# Power_Supply.net
KiCad netlist of a schematic drawn in Altium Designer
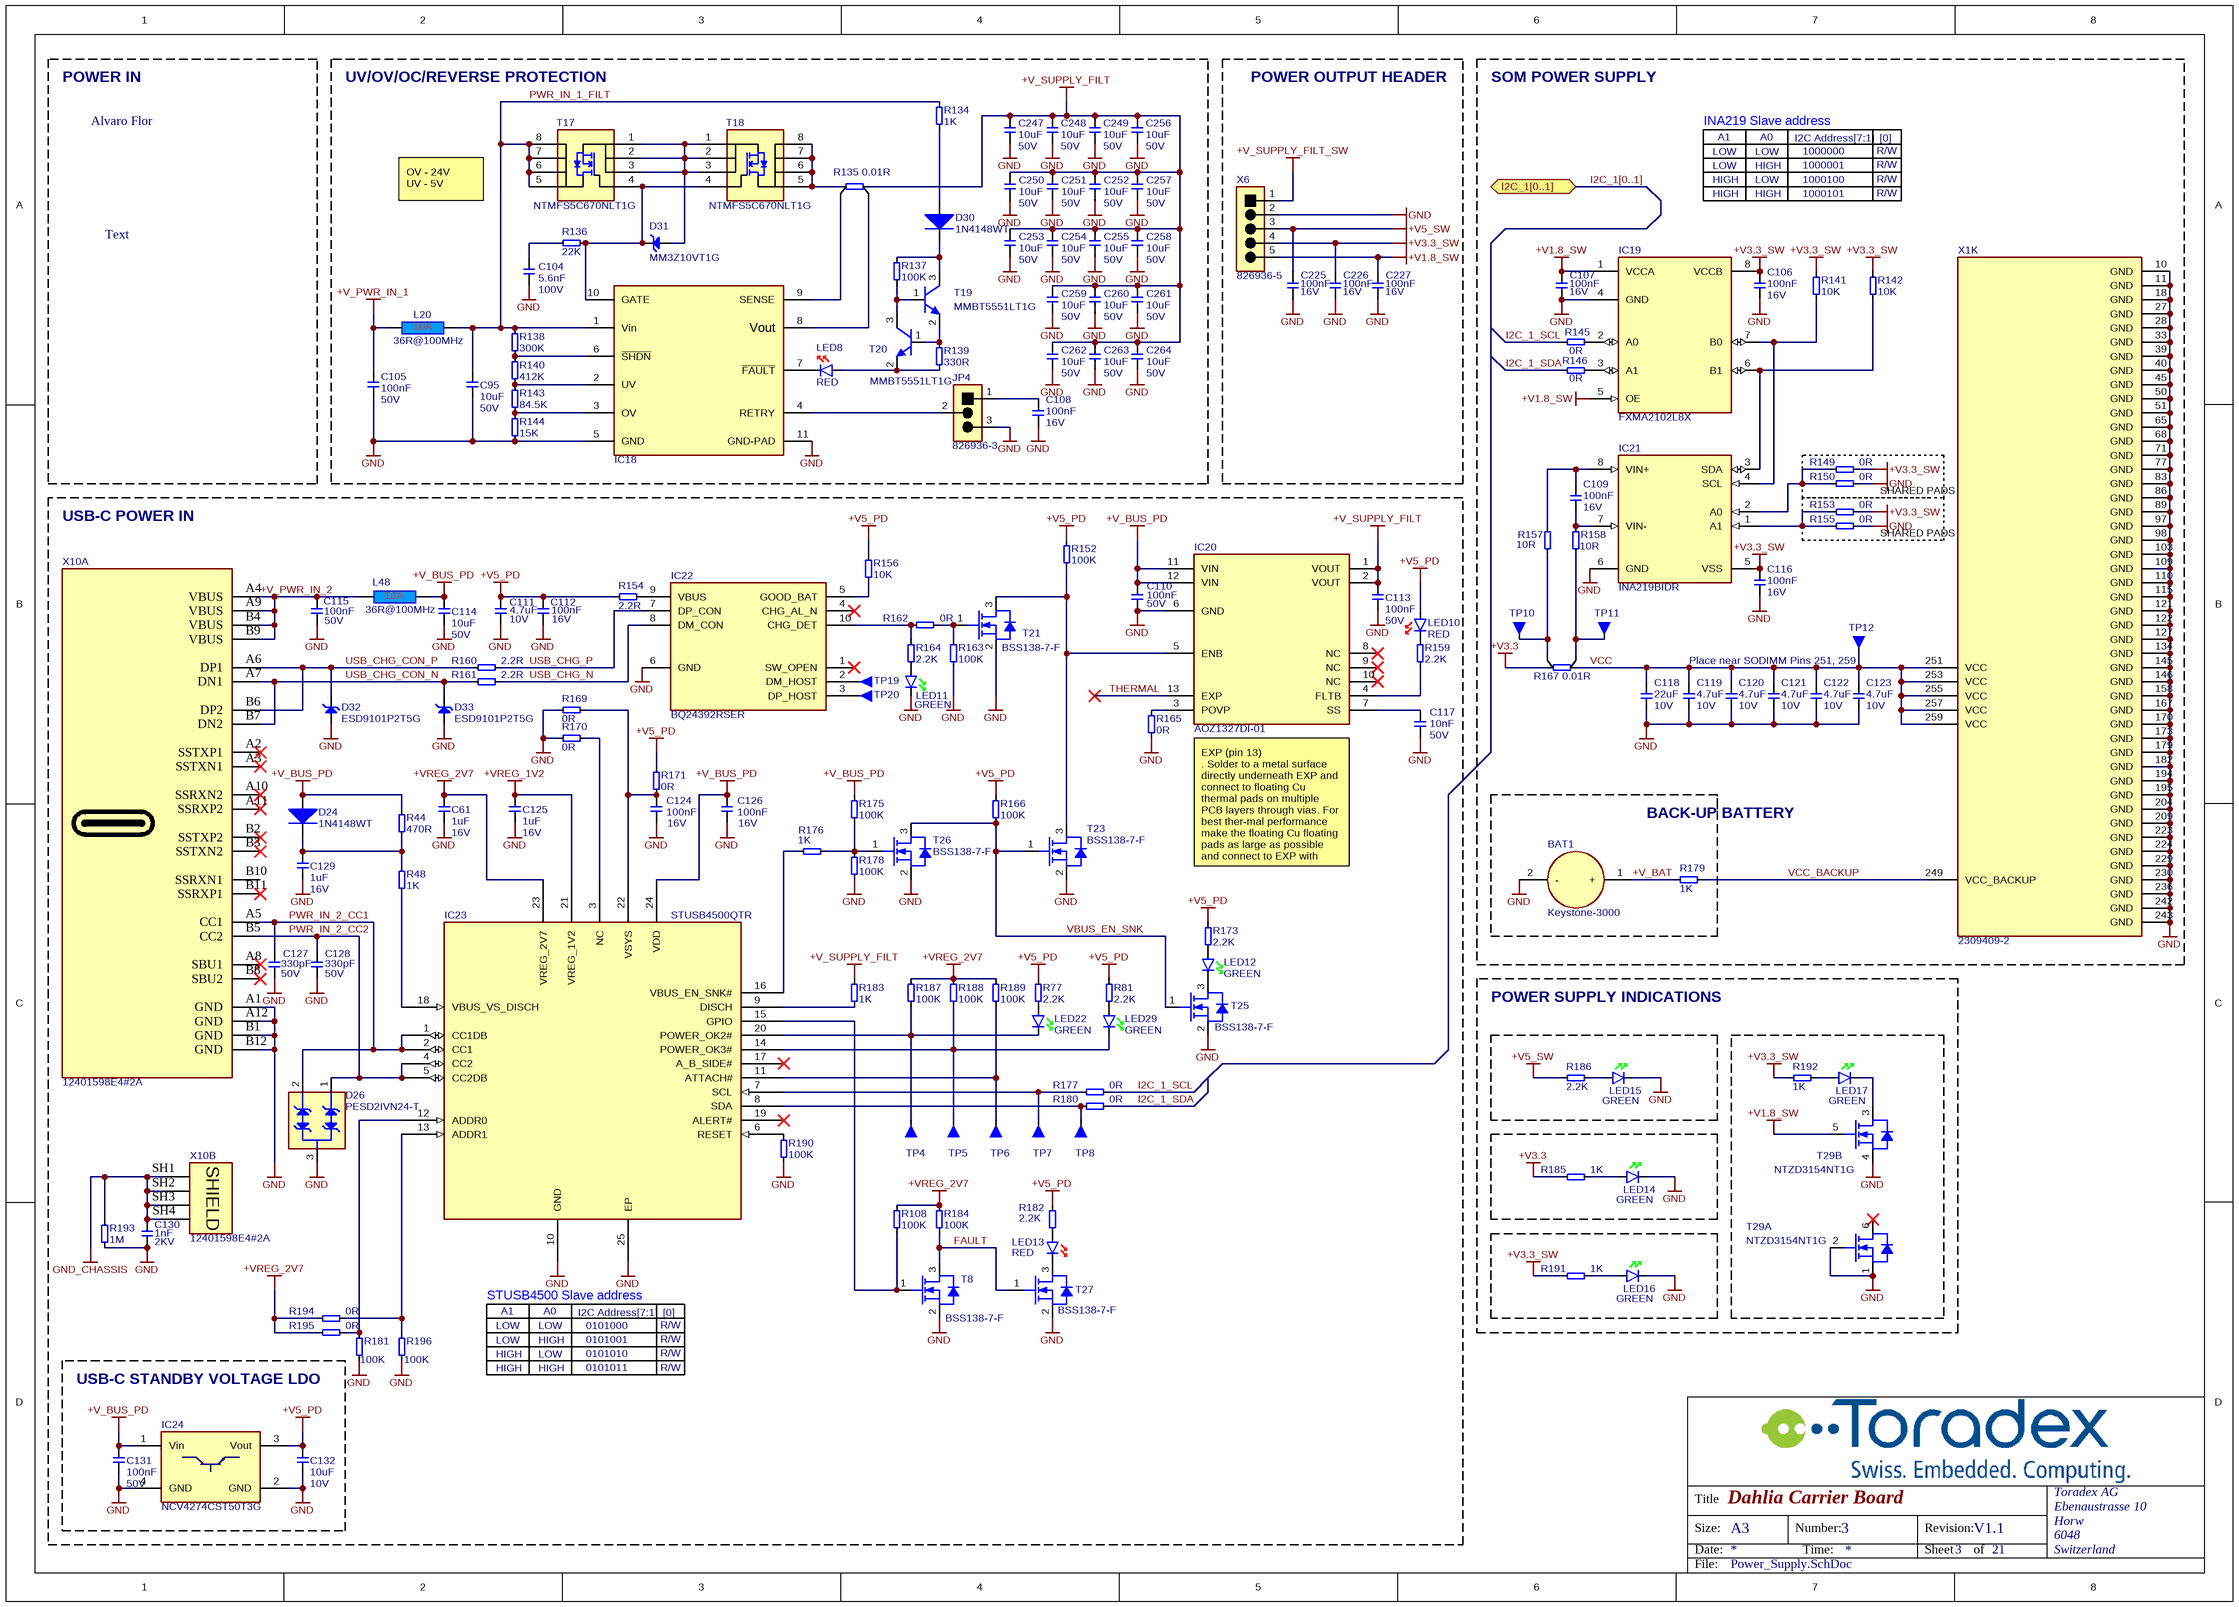
[diagram p0: Power_Supply.SchDoc]

(export (version "E")
  (design (tool "Eeschema 10.0.6"))
  (components
    (comp (ref "BAT1")
      (value "Keystone-3000")
      (footprint "T_Keystone_3000")
      (description "Battery Holder")
      (fields (field (name "MANUFACTURER PART NO.") "3000"))
      (libsource (lib "Dahlia Carrier Board") (part "BAT-Keystone-3000"))
    )
    (comp (ref "C61")
      (value "1uF")
      (footprint "CAPC1005X60N")
      (description "Capacitor Ceramic X5R 1uF 16V 20% 0402")
      (fields (field (name "TOLERANCE") "20%") (field (name "RATING") "16V"))
      (libsource (lib "Dahlia Carrier Board") (part "C-X5R-1uF-16V-20%-0402"))
    )
    (comp (ref "C95")
      (value "10uF")
      (footprint "T_CAPC1206X60N")
      (description "Capacitor Ceramic X5R 10uF 50V 20% 1206")
      (fields (field (name "TOLERANCE") "20%") (field (name "RATING") "50V"))
      (libsource (lib "Dahlia Carrier Board") (part "C-X5R-10uF-50V-20%-1206"))
    )
    (comp (ref "C104")
      (value "5.6nF")
      (footprint "T_CAPC1206X180N")
      (description "Capacitor Ceramic X7R 5.6nF 100V 10% 1206")
      (fields (field (name "TOLERANCE") "10%") (field (name "RATING") "100V"))
      (libsource (lib "Dahlia Carrier Board") (part "C-X7R-5.6n-100V-10%-1206"))
    )
    (comp (ref "C105")
      (value "100nF")
      (footprint "CAPC1005X60N")
      (description "Capacitor Ceramic X7R 100nF 50V 10% 0402")
      (fields (field (name "TOLERANCE") "10%") (field (name "RATING") "50V"))
      (libsource (lib "Dahlia Carrier Board") (part "C-X7R-100nF-50V-10%-0402"))
    )
    (comp (ref "C106")
      (value "100nF")
      (footprint "CAPC1005X60N")
      (description "Capacitor Ceramic X7R 100nF 16V 10% 0402")
      (fields (field (name "TOLERANCE") "10%") (field (name "RATING") "16V"))
      (libsource (lib "Dahlia Carrier Board") (part "C-X7R-100nF-16V-10%-0402"))
    )
    (comp (ref "C107")
      (value "100nF")
      (footprint "CAPC1005X60N")
      (description "Capacitor Ceramic X7R 100nF 16V 10% 0402")
      (fields (field (name "TOLERANCE") "10%") (field (name "RATING") "16V"))
      (libsource (lib "Dahlia Carrier Board") (part "C-X7R-100nF-16V-10%-0402"))
    )
    (comp (ref "C108")
      (value "100nF")
      (footprint "CAPC1005X60N")
      (description "Capacitor Ceramic X7R 100nF 16V 10% 0402")
      (fields (field (name "TOLERANCE") "10%") (field (name "RATING") "16V"))
      (libsource (lib "Dahlia Carrier Board") (part "C-X7R-100nF-16V-10%-0402"))
    )
    (comp (ref "C109")
      (value "100nF")
      (footprint "CAPC1005X60N")
      (description "Capacitor Ceramic X7R 100nF 16V 10% 0402")
      (fields (field (name "TOLERANCE") "10%") (field (name "RATING") "16V"))
      (libsource (lib "Dahlia Carrier Board") (part "C-X7R-100nF-16V-10%-0402"))
    )
    (comp (ref "C110")
      (value "100nF")
      (footprint "CAPC1005X60N")
      (description "Capacitor Ceramic X7R 100nF 50V 10% 0402")
      (fields (field (name "TOLERANCE") "10%") (field (name "RATING") "50V"))
      (libsource (lib "Dahlia Carrier Board") (part "C-X7R-100nF-50V-10%-0402"))
    )
    (comp (ref "C111")
      (value "4.7uF")
      (footprint "T_CAPC0603X33N")
      (description "Capacitor Ceramic X5R 4.7uF 10V 10% 0603")
      (fields (field (name "TOLERANCE") "10%") (field (name "RATING") "10V"))
      (libsource (lib "Dahlia Carrier Board") (part "C-X5R-4.7uF-10V-10%-0603"))
    )
    (comp (ref "C112")
      (value "100nF")
      (footprint "CAPC1005X60N")
      (description "Capacitor Ceramic X7R 100nF 16V 10% 0402")
      (fields (field (name "TOLERANCE") "10%") (field (name "RATING") "16V"))
      (libsource (lib "Dahlia Carrier Board") (part "C-X7R-100nF-16V-10%-0402"))
    )
    (comp (ref "C113")
      (value "100nF")
      (footprint "CAPC1005X60N")
      (description "Capacitor Ceramic X7R 100nF 50V 10% 0402")
      (fields (field (name "TOLERANCE") "10%") (field (name "RATING") "50V"))
      (libsource (lib "Dahlia Carrier Board") (part "C-X7R-100nF-50V-10%-0402"))
    )
    (comp (ref "C114")
      (value "10uF")
      (footprint "T_CAPC1206X60N")
      (description "Capacitor Ceramic X5R 10uF 50V 20% 1206")
      (fields (field (name "TOLERANCE") "20%") (field (name "RATING") "50V"))
      (libsource (lib "Dahlia Carrier Board") (part "C-X5R-10uF-50V-20%-1206"))
    )
    (comp (ref "C115")
      (value "100nF")
      (footprint "CAPC1005X60N")
      (description "Capacitor Ceramic X7R 100nF 50V 10% 0402")
      (fields (field (name "TOLERANCE") "10%") (field (name "RATING") "50V"))
      (libsource (lib "Dahlia Carrier Board") (part "C-X7R-100nF-50V-10%-0402"))
    )
    (comp (ref "C116")
      (value "100nF")
      (footprint "CAPC1005X60N")
      (description "Capacitor Ceramic X7R 100nF 16V 10% 0402")
      (fields (field (name "TOLERANCE") "10%") (field (name "RATING") "16V"))
      (libsource (lib "Dahlia Carrier Board") (part "C-X7R-100nF-16V-10%-0402"))
    )
    (comp (ref "C117")
      (value "10nF")
      (footprint "CAPC1005X60N")
      (description "Capacitor Ceramic X7R 10nF 50V 10% 0402")
      (fields (field (name "TOLERANCE") "10%") (field (name "RATING") "50V"))
      (libsource (lib "Dahlia Carrier Board") (part "C-X7R-10nF-50V-10%-0402"))
    )
    (comp (ref "C118")
      (value "22uF")
      (footprint "T_CAPC0805X125N")
      (description "Capacitor Ceramic X5R 22uF 10V 20% 0805")
      (fields (field (name "TOLERANCE") "20%") (field (name "RATING") "10V"))
      (libsource (lib "Dahlia Carrier Board") (part "C-X5R-22uF-10V-20%-0805"))
    )
    (comp (ref "C119")
      (value "4.7uF")
      (footprint "T_CAPC0603X33N")
      (description "Capacitor Ceramic X5R 4.7uF 10V 10% 0603")
      (fields (field (name "TOLERANCE") "10%") (field (name "RATING") "10V"))
      (libsource (lib "Dahlia Carrier Board") (part "C-X5R-4.7uF-10V-10%-0603"))
    )
    (comp (ref "C120")
      (value "4.7uF")
      (footprint "T_CAPC0603X33N")
      (description "Capacitor Ceramic X5R 4.7uF 10V 10% 0603")
      (fields (field (name "TOLERANCE") "10%") (field (name "RATING") "10V"))
      (libsource (lib "Dahlia Carrier Board") (part "C-X5R-4.7uF-10V-10%-0603"))
    )
    (comp (ref "C121")
      (value "4.7uF")
      (footprint "T_CAPC0603X33N")
      (description "Capacitor Ceramic X5R 4.7uF 10V 10% 0603")
      (fields (field (name "TOLERANCE") "10%") (field (name "RATING") "10V"))
      (libsource (lib "Dahlia Carrier Board") (part "C-X5R-4.7uF-10V-10%-0603"))
    )
    (comp (ref "C122")
      (value "4.7uF")
      (footprint "T_CAPC0603X33N")
      (description "Capacitor Ceramic X5R 4.7uF 10V 10% 0603")
      (fields (field (name "TOLERANCE") "10%") (field (name "RATING") "10V"))
      (libsource (lib "Dahlia Carrier Board") (part "C-X5R-4.7uF-10V-10%-0603"))
    )
    (comp (ref "C123")
      (value "4.7uF")
      (footprint "T_CAPC0603X33N")
      (description "Capacitor Ceramic X5R 4.7uF 10V 10% 0603")
      (fields (field (name "TOLERANCE") "10%") (field (name "RATING") "10V"))
      (libsource (lib "Dahlia Carrier Board") (part "C-X5R-4.7uF-10V-10%-0603"))
    )
    (comp (ref "C124")
      (value "100nF")
      (footprint "CAPC1005X60N")
      (description "Capacitor Ceramic X7R 100nF 16V 10% 0402")
      (fields (field (name "TOLERANCE") "10%") (field (name "RATING") "16V"))
      (libsource (lib "Dahlia Carrier Board") (part "C-X7R-100nF-16V-10%-0402"))
    )
    (comp (ref "C125")
      (value "1uF")
      (footprint "CAPC1005X60N")
      (description "Capacitor Ceramic X5R 1uF 16V 20% 0402")
      (fields (field (name "TOLERANCE") "20%") (field (name "RATING") "16V"))
      (libsource (lib "Dahlia Carrier Board") (part "C-X5R-1uF-16V-20%-0402"))
    )
    (comp (ref "C126")
      (value "100nF")
      (footprint "CAPC1005X60N")
      (description "Capacitor Ceramic X7R 100nF 16V 10% 0402")
      (fields (field (name "TOLERANCE") "10%") (field (name "RATING") "16V"))
      (libsource (lib "Dahlia Carrier Board") (part "C-X7R-100nF-16V-10%-0402"))
    )
    (comp (ref "C127")
      (value "330pF")
      (footprint "CAPC1005X60N")
      (description "Capacitor Ceramic X7R 330pF 50V 10% 0402")
      (fields (field (name "TOLERANCE") "10%") (field (name "RATING") "50V"))
      (libsource (lib "Dahlia Carrier Board") (part "C-X7R-330pF-50V-10%-0402"))
    )
    (comp (ref "C128")
      (value "330pF")
      (footprint "CAPC1005X60N")
      (description "Capacitor Ceramic X7R 330pF 50V 10% 0402")
      (fields (field (name "TOLERANCE") "10%") (field (name "RATING") "50V"))
      (libsource (lib "Dahlia Carrier Board") (part "C-X7R-330pF-50V-10%-0402"))
    )
    (comp (ref "C129")
      (value "1uF")
      (footprint "CAPC1005X60N")
      (description "Capacitor Ceramic X5R 1uF 16V 20% 0402")
      (fields (field (name "TOLERANCE") "20%") (field (name "RATING") "16V"))
      (libsource (lib "Dahlia Carrier Board") (part "C-X5R-1uF-16V-20%-0402"))
    )
    (comp (ref "C130")
      (value "1nF")
      (footprint "T_CAPC1206X180N")
      (description "Capacitor Ceramic X7R 1nF 2KV 10% 1206")
      (fields (field (name "TOLERANCE") "10%") (field (name "RATING") "2KV"))
      (libsource (lib "Dahlia Carrier Board") (part "C-X7R-1nF-2KV-10%-1206"))
    )
    (comp (ref "C131")
      (value "100nF")
      (footprint "CAPC1005X60N")
      (description "Capacitor Ceramic X7R 100nF 50V 10% 0402")
      (fields (field (name "TOLERANCE") "10%") (field (name "RATING") "50V"))
      (libsource (lib "Dahlia Carrier Board") (part "C-X7R-100nF-50V-10%-0402"))
    )
    (comp (ref "C132")
      (value "10uF")
      (footprint "T_CAPC0603X33N")
      (description "Capacitor Ceramic X5R 10uF 10V 20% 0603")
      (fields (field (name "TOLERANCE") "20%") (field (name "RATING") "10V"))
      (libsource (lib "Dahlia Carrier Board") (part "C-X5R-10uF-10V-20%-0603"))
    )
    (comp (ref "C225")
      (value "100nF")
      (footprint "CAPC1005X60N")
      (description "Capacitor Ceramic X7R 100nF 16V 10% 0402")
      (fields (field (name "TOLERANCE") "10%") (field (name "RATING") "16V"))
      (libsource (lib "Dahlia Carrier Board") (part "C-X7R-100nF-16V-10%-0402"))
    )
    (comp (ref "C226")
      (value "100nF")
      (footprint "CAPC1005X60N")
      (description "Capacitor Ceramic X7R 100nF 16V 10% 0402")
      (fields (field (name "TOLERANCE") "10%") (field (name "RATING") "16V"))
      (libsource (lib "Dahlia Carrier Board") (part "C-X7R-100nF-16V-10%-0402"))
    )
    (comp (ref "C227")
      (value "100nF")
      (footprint "CAPC1005X60N")
      (description "Capacitor Ceramic X7R 100nF 16V 10% 0402")
      (fields (field (name "TOLERANCE") "10%") (field (name "RATING") "16V"))
      (libsource (lib "Dahlia Carrier Board") (part "C-X7R-100nF-16V-10%-0402"))
    )
    (comp (ref "C247")
      (value "10uF")
      (footprint "T_CAPC1206X60N")
      (description "Capacitor Ceramic X5R 10uF 50V 20% 1206")
      (fields (field (name "TOLERANCE") "20%") (field (name "RATING") "50V"))
      (libsource (lib "Dahlia Carrier Board") (part "C-X5R-10uF-50V-20%-1206"))
    )
    (comp (ref "C248")
      (value "10uF")
      (footprint "T_CAPC1206X60N")
      (description "Capacitor Ceramic X5R 10uF 50V 20% 1206")
      (fields (field (name "TOLERANCE") "20%") (field (name "RATING") "50V"))
      (libsource (lib "Dahlia Carrier Board") (part "C-X5R-10uF-50V-20%-1206"))
    )
    (comp (ref "C249")
      (value "10uF")
      (footprint "T_CAPC1206X60N")
      (description "Capacitor Ceramic X5R 10uF 50V 20% 1206")
      (fields (field (name "TOLERANCE") "20%") (field (name "RATING") "50V"))
      (libsource (lib "Dahlia Carrier Board") (part "C-X5R-10uF-50V-20%-1206"))
    )
    (comp (ref "C250")
      (value "10uF")
      (footprint "T_CAPC1206X60N")
      (description "Capacitor Ceramic X5R 10uF 50V 20% 1206")
      (fields (field (name "TOLERANCE") "20%") (field (name "RATING") "50V"))
      (libsource (lib "Dahlia Carrier Board") (part "C-X5R-10uF-50V-20%-1206"))
    )
    (comp (ref "C251")
      (value "10uF")
      (footprint "T_CAPC1206X60N")
      (description "Capacitor Ceramic X5R 10uF 50V 20% 1206")
      (fields (field (name "TOLERANCE") "20%") (field (name "RATING") "50V"))
      (libsource (lib "Dahlia Carrier Board") (part "C-X5R-10uF-50V-20%-1206"))
    )
    (comp (ref "C252")
      (value "10uF")
      (footprint "T_CAPC1206X60N")
      (description "Capacitor Ceramic X5R 10uF 50V 20% 1206")
      (fields (field (name "TOLERANCE") "20%") (field (name "RATING") "50V"))
      (libsource (lib "Dahlia Carrier Board") (part "C-X5R-10uF-50V-20%-1206"))
    )
    (comp (ref "C253")
      (value "10uF")
      (footprint "T_CAPC1206X60N")
      (description "Capacitor Ceramic X5R 10uF 50V 20% 1206")
      (fields (field (name "TOLERANCE") "20%") (field (name "RATING") "50V"))
      (libsource (lib "Dahlia Carrier Board") (part "C-X5R-10uF-50V-20%-1206"))
    )
    (comp (ref "C254")
      (value "10uF")
      (footprint "T_CAPC1206X60N")
      (description "Capacitor Ceramic X5R 10uF 50V 20% 1206")
      (fields (field (name "TOLERANCE") "20%") (field (name "RATING") "50V"))
      (libsource (lib "Dahlia Carrier Board") (part "C-X5R-10uF-50V-20%-1206"))
    )
    (comp (ref "C255")
      (value "10uF")
      (footprint "T_CAPC1206X60N")
      (description "Capacitor Ceramic X5R 10uF 50V 20% 1206")
      (fields (field (name "TOLERANCE") "20%") (field (name "RATING") "50V"))
      (libsource (lib "Dahlia Carrier Board") (part "C-X5R-10uF-50V-20%-1206"))
    )
    (comp (ref "C256")
      (value "10uF")
      (footprint "T_CAPC1206X60N")
      (description "Capacitor Ceramic X5R 10uF 50V 20% 1206")
      (fields (field (name "TOLERANCE") "20%") (field (name "RATING") "50V"))
      (libsource (lib "Dahlia Carrier Board") (part "C-X5R-10uF-50V-20%-1206"))
    )
    (comp (ref "C257")
      (value "10uF")
      (footprint "T_CAPC1206X60N")
      (description "Capacitor Ceramic X5R 10uF 50V 20% 1206")
      (fields (field (name "TOLERANCE") "20%") (field (name "RATING") "50V"))
      (libsource (lib "Dahlia Carrier Board") (part "C-X5R-10uF-50V-20%-1206"))
    )
    (comp (ref "C258")
      (value "10uF")
      (footprint "T_CAPC1206X60N")
      (description "Capacitor Ceramic X5R 10uF 50V 20% 1206")
      (fields (field (name "TOLERANCE") "20%") (field (name "RATING") "50V"))
      (libsource (lib "Dahlia Carrier Board") (part "C-X5R-10uF-50V-20%-1206"))
    )
    (comp (ref "C259")
      (value "10uF")
      (footprint "T_CAPC1206X60N")
      (description "Capacitor Ceramic X5R 10uF 50V 20% 1206")
      (fields (field (name "TOLERANCE") "20%") (field (name "RATING") "50V"))
      (libsource (lib "Dahlia Carrier Board") (part "C-X5R-10uF-50V-20%-1206"))
    )
    (comp (ref "C260")
      (value "10uF")
      (footprint "T_CAPC1206X60N")
      (description "Capacitor Ceramic X5R 10uF 50V 20% 1206")
      (fields (field (name "TOLERANCE") "20%") (field (name "RATING") "50V"))
      (libsource (lib "Dahlia Carrier Board") (part "C-X5R-10uF-50V-20%-1206"))
    )
    (comp (ref "C261")
      (value "10uF")
      (footprint "T_CAPC1206X60N")
      (description "Capacitor Ceramic X5R 10uF 50V 20% 1206")
      (fields (field (name "TOLERANCE") "20%") (field (name "RATING") "50V"))
      (libsource (lib "Dahlia Carrier Board") (part "C-X5R-10uF-50V-20%-1206"))
    )
    (comp (ref "C262")
      (value "10uF")
      (footprint "T_CAPC1206X60N")
      (description "Capacitor Ceramic X5R 10uF 50V 20% 1206")
      (fields (field (name "TOLERANCE") "20%") (field (name "RATING") "50V"))
      (libsource (lib "Dahlia Carrier Board") (part "C-X5R-10uF-50V-20%-1206"))
    )
    (comp (ref "C263")
      (value "10uF")
      (footprint "T_CAPC1206X60N")
      (description "Capacitor Ceramic X5R 10uF 50V 20% 1206")
      (fields (field (name "TOLERANCE") "20%") (field (name "RATING") "50V"))
      (libsource (lib "Dahlia Carrier Board") (part "C-X5R-10uF-50V-20%-1206"))
    )
    (comp (ref "C264")
      (value "10uF")
      (footprint "T_CAPC1206X60N")
      (description "Capacitor Ceramic X5R 10uF 50V 20% 1206")
      (fields (field (name "TOLERANCE") "20%") (field (name "RATING") "50V"))
      (libsource (lib "Dahlia Carrier Board") (part "C-X5R-10uF-50V-20%-1206"))
    )
    (comp (ref "D24")
      (value "1N4148WT")
      (footprint "SOD-523F")
      (description "Diode Standard 75V 200mA Surface Mount SOD-523F")
      (fields (field (name "MANUFACTURER PART NO.") "1N4148WT"))
      (libsource (lib "Dahlia Carrier Board") (part "D-OnSemi-1N4148WT"))
    )
    (comp (ref "D26")
      (value "PESD2IVN24-T")
      (footprint "SOT95P230X110-3N")
      (description "TVS Array low cap")
      (fields (field (name "MANUFACTURER PART NO.") "PESD2IVN24-T"))
      (libsource (lib "Dahlia Carrier Board") (part "D-Nexperia-PESD2IVN24-T"))
    )
    (comp (ref "D30")
      (value "1N4148WT")
      (footprint "SOD-523F")
      (description "Diode Standard 75V 200mA Surface Mount SOD-523F")
      (fields (field (name "MANUFACTURER PART NO.") "1N4148WT"))
      (libsource (lib "Dahlia Carrier Board") (part "D-OnSemi-1N4148WT"))
    )
    (comp (ref "D31")
      (value "MM3Z10VT1G")
      (footprint "T_SOD-323")
      (description "DIODE ZENER 10V 300MW SOD323")
      (fields (field (name "MANUFACTURER PART NO.") "MM3Z10VT1G"))
      (libsource (lib "Dahlia Carrier Board") (part "D-OnSemi-MM3Z10VT1G"))
    )
    (comp (ref "D32")
      (value "ESD9101P2T5G")
      (footprint "SOD-923")
      (description "ESD Protection Diode")
      (fields (field (name "MANUFACTURER PART NO.") "ESD9101P2T5G"))
      (libsource (lib "Dahlia Carrier Board") (part "D-OnSemi-ESD9101P2T5G"))
    )
    (comp (ref "D33")
      (value "ESD9101P2T5G")
      (footprint "SOD-923")
      (description "ESD Protection Diode")
      (fields (field (name "MANUFACTURER PART NO.") "ESD9101P2T5G"))
      (libsource (lib "Dahlia Carrier Board") (part "D-OnSemi-ESD9101P2T5G"))
    )
    (comp (ref "IC18")
      (value "LTC4368IDD-2#PBF")
      (footprint "IC-DFN50P300X300X75-10N")
      (description "Reverse Protection Controller with Bidirectional Circuit Breaker")
      (libsource (lib "Dahlia Carrier Board") (part "IC-LIN-LTC4368IDD-2#PBF"))
    )
    (comp (ref "IC19")
      (value "FXMA2102L8X")
      (footprint "IC-MicroPak50P160X2160X55-8N")
      (description "Voltage Level Translator for I2C Applications")
      (fields (field (name "MANUFACTURER PART NO.") "FXMA2102L8X"))
      (libsource (lib "Dahlia Carrier Board") (part "IC-ONsemi-FXMA2102L8X"))
    )
    (comp (ref "IC20")
      (value "AOZ1327DI-01")
      (footprint "IC-A&O-AOZ1327DI-01")
      (description "20V Protection Switch with True Reverse Current Blocking")
      (fields (field (name "MANUFACTURER PART NO.") "AOZ1327DI-01"))
      (libsource (lib "Dahlia Carrier Board") (part "IC-A&O-AOZ1327DI-01"))
    )
    (comp (ref "IC21")
      (value "INA219")
      (footprint "SOIC127P600X173-8N")
      (description "CURRENT/POWER MONITOR with I2C Interface")
      (fields (field (name "MANUFACTURER PART NO.") "INA219BIDR"))
      (libsource (lib "Dahlia Carrier Board") (part "IC-TI-INA219BIDR"))
    )
    (comp (ref "IC22")
      (value "BQ24392RSER")
      (footprint "IC-TI-BQ24392RSER")
      (description "USB Charger Detection")
      (fields (field (name "MANUFACTURER PART NO.") "BQ24392RSER"))
      (libsource (lib "Dahlia Carrier Board") (part "IC-TI-BQ24392RSER"))
    )
    (comp (ref "IC23")
      (value "STUSB4500QTR")
      (footprint "T_STUSB4500QTR")
      (description "Standalone USB PD sink controller with short-to-VBUS protections")
      (libsource (lib "Dahlia Carrier Board") (part "IC-ST-STUSB4500QTR"))
    )
    (comp (ref "IC24")
      (value "NCV4274CST50T3G")
      (footprint "T_ON_NCV4264-2ST50T3G")
      (description "LDO regulator, Vout = 5V, Iout(max) = 0.4A, Vin = 5.5V to 40V, SOT-223")
      (fields (field (name "MANUFACTURER PART NO.") "NCV4274CST50T3G"))
      (libsource (lib "Dahlia Carrier Board") (part "IC-ON-NCV4274CST50T3G"))
    )
    (comp (ref "JP4")
      (value "826936-3")
      (footprint "T_TYCO_826936-3")
      (description "Jumper, 3-Pin")
      (fields (field (name "MANUFACTURER PART NO.") "826936-3"))
      (libsource (lib "Dahlia Carrier Board") (part "CON-Tyco-826936-3-1X3-2.54mm-JP_1"))
    )
    (comp (ref "L20")
      (value "36R@100MHz")
      (footprint "T_Laird_35F0121-0SR-10")
      (description "Power Supply FB 10A")
      (fields (field (name "TOLERANCE") "25%"))
      (libsource (lib "Dahlia Carrier Board") (part "L-Laird-35F0121-0SR-10-10A-25%"))
    )
    (comp (ref "L48")
      (value "36R@100MHz")
      (footprint "T_Laird_35F0121-0SR-10")
      (description "Power Supply FB 10A")
      (fields (field (name "TOLERANCE") "25%"))
      (libsource (lib "Dahlia Carrier Board") (part "L-Laird-35F0121-0SR-10-10A-25%"))
    )
    (comp (ref "LED8")
      (value "LTST-C190KRKT")
      (footprint "T_Liteon_LTST-C190KRKT")
      (description "LED red, Lite-On LTST-C190KRKT")
      (fields (field (name "COLOR") "RED"))
      (libsource (lib "Dahlia Carrier Board") (part "LED-LiteOn-LTST-C190KRKT"))
    )
    (comp (ref "LED10")
      (value "LTST-C190KRKT")
      (footprint "T_Liteon_LTST-C190KRKT")
      (description "LED red, Lite-On LTST-C190KRKT")
      (fields (field (name "COLOR") "RED"))
      (libsource (lib "Dahlia Carrier Board") (part "LED-LiteOn-LTST-C190KRKT"))
    )
    (comp (ref "LED11")
      (value "LTST-C190GKT")
      (footprint "T_Liteon_LTST-C190GKT")
      (description "LED green Lite-ON LTST-C190GKT")
      (fields (field (name "COLOR") "GREEN"))
      (libsource (lib "Dahlia Carrier Board") (part "LED-LiteOn-LTST-C190GKT"))
    )
    (comp (ref "LED12")
      (value "LTST-C190GKT")
      (footprint "T_Liteon_LTST-C190GKT")
      (description "LED green Lite-ON LTST-C190GKT")
      (fields (field (name "COLOR") "GREEN"))
      (libsource (lib "Dahlia Carrier Board") (part "LED-LiteOn-LTST-C190GKT"))
    )
    (comp (ref "LED13")
      (value "LTST-C190KRKT")
      (footprint "T_Liteon_LTST-C190KRKT")
      (description "LED red, Lite-On LTST-C190KRKT")
      (fields (field (name "COLOR") "RED"))
      (libsource (lib "Dahlia Carrier Board") (part "LED-LiteOn-LTST-C190KRKT"))
    )
    (comp (ref "LED14")
      (value "LTST-C190GKT")
      (footprint "T_Liteon_LTST-C190GKT")
      (description "LED green Lite-ON LTST-C190GKT")
      (fields (field (name "COLOR") "GREEN"))
      (libsource (lib "Dahlia Carrier Board") (part "LED-LiteOn-LTST-C190GKT"))
    )
    (comp (ref "LED15")
      (value "LTST-C190GKT")
      (footprint "T_Liteon_LTST-C190GKT")
      (description "LED green Lite-ON LTST-C190GKT")
      (fields (field (name "COLOR") "GREEN"))
      (libsource (lib "Dahlia Carrier Board") (part "LED-LiteOn-LTST-C190GKT"))
    )
    (comp (ref "LED16")
      (value "LTST-C190GKT")
      (footprint "T_Liteon_LTST-C190GKT")
      (description "LED green Lite-ON LTST-C190GKT")
      (fields (field (name "COLOR") "GREEN"))
      (libsource (lib "Dahlia Carrier Board") (part "LED-LiteOn-LTST-C190GKT"))
    )
    (comp (ref "LED17")
      (value "LTST-C190GKT")
      (footprint "T_Liteon_LTST-C190GKT")
      (description "LED green Lite-ON LTST-C190GKT")
      (fields (field (name "COLOR") "GREEN"))
      (libsource (lib "Dahlia Carrier Board") (part "LED-LiteOn-LTST-C190GKT"))
    )
    (comp (ref "LED22")
      (value "LTST-C190GKT")
      (footprint "T_Liteon_LTST-C190GKT")
      (description "LED green Lite-ON LTST-C190GKT")
      (fields (field (name "COLOR") "GREEN"))
      (libsource (lib "Dahlia Carrier Board") (part "LED-LiteOn-LTST-C190GKT"))
    )
    (comp (ref "LED29")
      (value "LTST-C190GKT")
      (footprint "T_Liteon_LTST-C190GKT")
      (description "LED green Lite-ON LTST-C190GKT")
      (fields (field (name "COLOR") "GREEN"))
      (libsource (lib "Dahlia Carrier Board") (part "LED-LiteOn-LTST-C190GKT"))
    )
    (comp (ref "R44")
      (value "470R")
      (footprint "T_RESC0603X30N")
      (description "Resistor 470 Ohm 63mW 1% 0603")
      (fields (field (name "TOLERANCE") "1%"))
      (libsource (lib "Dahlia Carrier Board") (part "R-470R-63mW-1%-0603"))
    )
    (comp (ref "R48")
      (value "1K")
      (footprint "T_RESC0603X30N")
      (description "Resistor 1 Kohm 63mW 5% 0603")
      (fields (field (name "TOLERANCE") "5%"))
      (libsource (lib "Dahlia Carrier Board") (part "R-1K-63mW-5%-0603"))
    )
    (comp (ref "R77")
      (value "2.2K")
      (footprint "RESC1005X40N")
      (description "Resistor 2.2 Kohm 63mW 5% 0402")
      (fields (field (name "TOLERANCE") "5%"))
      (libsource (lib "Dahlia Carrier Board") (part "R-2.2K-63mW-5%-0402"))
    )
    (comp (ref "R81")
      (value "2.2K")
      (footprint "RESC1005X40N")
      (description "Resistor 2.2 Kohm 63mW 5% 0402")
      (fields (field (name "TOLERANCE") "5%"))
      (libsource (lib "Dahlia Carrier Board") (part "R-2.2K-63mW-5%-0402"))
    )
    (comp (ref "R108")
      (value "100K")
      (footprint "RESC1005X40N")
      (description "Resistor 100 Kohm 63mW 5% 0402")
      (fields (field (name "TOLERANCE") "5%"))
      (libsource (lib "Dahlia Carrier Board") (part "R-100K-63mW-5%-0402"))
    )
    (comp (ref "R134")
      (value "1K")
      (footprint "RESC1005X40N")
      (description "Resistor 1 Kohm 63mW 5% 0402")
      (fields (field (name "TOLERANCE") "5%"))
      (libsource (lib "Dahlia Carrier Board") (part "R-1K-63mW-5%-0402"))
    )
    (comp (ref "R135")
      (value "0.01R")
      (footprint "RESWSK1206")
      (fields (field (name "TOLERANCE") "1%") (field (name "MANUFACTURER PART NO.") "WSK1206R0100FEA18"))
      (libsource (lib "Dahlia Carrier Board") (part "R-Vishay-WSK1206R0100FEA18"))
    )
    (comp (ref "R136")
      (value "22K")
      (footprint "RESC3216X75N")
      (description "Resistor 22 Kohm 250mW 1% 1206")
      (fields (field (name "TOLERANCE") "1%"))
      (libsource (lib "Dahlia Carrier Board") (part "R-22K-250mW-1%-1206"))
    )
    (comp (ref "R137")
      (value "100K")
      (footprint "RESC1005X40N")
      (description "Resistor 100 Kohm 63mW 5% 0402")
      (fields (field (name "TOLERANCE") "5%"))
      (libsource (lib "Dahlia Carrier Board") (part "R-100K-63mW-5%-0402"))
    )
    (comp (ref "R138")
      (value "300K")
      (footprint "RESC3216X75N")
      (description "Resistor 300 Kohm 250mW 1% 1206")
      (fields (field (name "TOLERANCE") "1%"))
      (libsource (lib "Dahlia Carrier Board") (part "R-300K-250mW-1%-1206"))
    )
    (comp (ref "R139")
      (value "330R")
      (footprint "RESC1005X40N")
      (description "Resistor 330 ohm 63mW 5% 0402")
      (fields (field (name "TOLERANCE") "5%"))
      (libsource (lib "Dahlia Carrier Board") (part "R-330R-63mW-5%-0402"))
    )
    (comp (ref "R140")
      (value "412K")
      (footprint "RESC3216X75N")
      (description "Resistor 412 Kohm 250mW 1% 1206")
      (fields (field (name "TOLERANCE") "1%"))
      (libsource (lib "Dahlia Carrier Board") (part "R-412K-250mW-1%-1206"))
    )
    (comp (ref "R141")
      (value "10K")
      (footprint "RESC1005X40N")
      (description "Resistor 10 Kohm 63mW 5% 0402")
      (fields (field (name "TOLERANCE") "5%"))
      (libsource (lib "Dahlia Carrier Board") (part "R-10K-63mW-5%-0402"))
    )
    (comp (ref "R142")
      (value "10K")
      (footprint "RESC1005X40N")
      (description "Resistor 10 Kohm 63mW 5% 0402")
      (fields (field (name "TOLERANCE") "5%"))
      (libsource (lib "Dahlia Carrier Board") (part "R-10K-63mW-5%-0402"))
    )
    (comp (ref "R143")
      (value "84.5K")
      (footprint "RESC3216X75N")
      (description "Resistor 84.5 Kohm 250mW 1% 1206")
      (fields (field (name "TOLERANCE") "1%"))
      (libsource (lib "Dahlia Carrier Board") (part "R-84.5K-250mW-1%-1206"))
    )
    (comp (ref "R144")
      (value "15K")
      (footprint "RESC3216X75N")
      (description "Resistor 15 Kohm 250mW 1% 1206")
      (fields (field (name "TOLERANCE") "1%"))
      (libsource (lib "Dahlia Carrier Board") (part "R-15K-250mW-1%-1206"))
    )
    (comp (ref "R145")
      (value "0R")
      (footprint "T_RESC0603X30N")
      (description "Resistor 0 ohm 63mW 1% 0603")
      (fields (field (name "TOLERANCE") "1%"))
      (libsource (lib "Dahlia Carrier Board") (part "R-0R-63mW-1%-0603"))
    )
    (comp (ref "R146")
      (value "0R")
      (footprint "T_RESC0603X30N")
      (description "Resistor 0 ohm 63mW 1% 0603")
      (fields (field (name "TOLERANCE") "1%"))
      (libsource (lib "Dahlia Carrier Board") (part "R-0R-63mW-1%-0603"))
    )
    (comp (ref "R149")
      (value "0R")
      (footprint "T_RESC0603X30N")
      (description "Resistor 0 ohm 63mW 1% 0603")
      (fields (field (name "TOLERANCE") "1%"))
      (libsource (lib "Dahlia Carrier Board") (part "R-0R-63mW-1%-0603"))
    )
    (comp (ref "R150")
      (value "0R")
      (footprint "T_RESC0603X30N")
      (description "Resistor 0 ohm 63mW 1% 0603")
      (fields (field (name "TOLERANCE") "1%"))
      (libsource (lib "Dahlia Carrier Board") (part "R-0R-63mW-1%-0603"))
    )
    (comp (ref "R152")
      (value "100K")
      (footprint "RESC1005X40N")
      (description "Resistor 100 Kohm 63mW 5% 0402")
      (fields (field (name "TOLERANCE") "5%"))
      (libsource (lib "Dahlia Carrier Board") (part "R-100K-63mW-5%-0402"))
    )
    (comp (ref "R153")
      (value "0R")
      (footprint "T_RESC0603X30N")
      (description "Resistor 0 ohm 63mW 1% 0603")
      (fields (field (name "TOLERANCE") "1%"))
      (libsource (lib "Dahlia Carrier Board") (part "R-0R-63mW-1%-0603"))
    )
    (comp (ref "R154")
      (value "2.2R")
      (footprint "T_RESC0603X30N")
      (description "Resistor 2.2 ohm 63mW 5% 0603")
      (fields (field (name "TOLERANCE") "5%"))
      (libsource (lib "Dahlia Carrier Board") (part "R-2.2R-63mW-5%-0603"))
    )
    (comp (ref "R155")
      (value "0R")
      (footprint "T_RESC0603X30N")
      (description "Resistor 0 ohm 63mW 1% 0603")
      (fields (field (name "TOLERANCE") "1%"))
      (libsource (lib "Dahlia Carrier Board") (part "R-0R-63mW-1%-0603"))
    )
    (comp (ref "R156")
      (value "10K")
      (footprint "RESC1005X40N")
      (description "Resistor 10 Kohm 63mW 5% 0402")
      (fields (field (name "TOLERANCE") "5%"))
      (libsource (lib "Dahlia Carrier Board") (part "R-10K-63mW-5%-0402"))
    )
    (comp (ref "R157")
      (value "10R")
      (footprint "RESC1005X40N")
      (description "Resistor 10 ohm 63mW 5% 0402")
      (fields (field (name "TOLERANCE") "5%"))
      (libsource (lib "Dahlia Carrier Board") (part "R-10R-63mW-5%-0402"))
    )
    (comp (ref "R158")
      (value "10R")
      (footprint "RESC1005X40N")
      (description "Resistor 10 ohm 63mW 5% 0402")
      (fields (field (name "TOLERANCE") "5%"))
      (libsource (lib "Dahlia Carrier Board") (part "R-10R-63mW-5%-0402"))
    )
    (comp (ref "R159")
      (value "2.2K")
      (footprint "RESC1005X40N")
      (description "Resistor 2.2 Kohm 63mW 5% 0402")
      (fields (field (name "TOLERANCE") "5%"))
      (libsource (lib "Dahlia Carrier Board") (part "R-2.2K-63mW-5%-0402"))
    )
    (comp (ref "R160")
      (value "2.2R")
      (footprint "T_RESC0603X30N")
      (description "Resistor 2.2 ohm 63mW 5% 0603")
      (fields (field (name "TOLERANCE") "5%"))
      (libsource (lib "Dahlia Carrier Board") (part "R-2.2R-63mW-5%-0603"))
    )
    (comp (ref "R161")
      (value "2.2R")
      (footprint "T_RESC0603X30N")
      (description "Resistor 2.2 ohm 63mW 5% 0603")
      (fields (field (name "TOLERANCE") "5%"))
      (libsource (lib "Dahlia Carrier Board") (part "R-2.2R-63mW-5%-0603"))
    )
    (comp (ref "R162")
      (value "0R")
      (footprint "T_RESC0603X30N")
      (description "Resistor 0 ohm 63mW 1% 0603")
      (fields (field (name "TOLERANCE") "1%"))
      (libsource (lib "Dahlia Carrier Board") (part "R-0R-63mW-1%-0603"))
    )
    (comp (ref "R163")
      (value "100K")
      (footprint "RESC1005X40N")
      (description "Resistor 100 Kohm 63mW 5% 0402")
      (fields (field (name "TOLERANCE") "5%"))
      (libsource (lib "Dahlia Carrier Board") (part "R-100K-63mW-5%-0402"))
    )
    (comp (ref "R164")
      (value "2.2K")
      (footprint "RESC1005X40N")
      (description "Resistor 2.2 Kohm 63mW 5% 0402")
      (fields (field (name "TOLERANCE") "5%"))
      (libsource (lib "Dahlia Carrier Board") (part "R-2.2K-63mW-5%-0402"))
    )
    (comp (ref "R165")
      (value "0R")
      (footprint "T_RESC0603X30N")
      (description "Resistor 0 ohm 63mW 1% 0603")
      (fields (field (name "TOLERANCE") "1%"))
      (libsource (lib "Dahlia Carrier Board") (part "R-0R-63mW-1%-0603"))
    )
    (comp (ref "R166")
      (value "100K")
      (footprint "RESC1005X40N")
      (description "Resistor 100 Kohm 63mW 5% 0402")
      (fields (field (name "TOLERANCE") "5%"))
      (libsource (lib "Dahlia Carrier Board") (part "R-100K-63mW-5%-0402"))
    )
    (comp (ref "R167")
      (value "0.01R")
      (footprint "RESWSK1206")
      (fields (field (name "TOLERANCE") "1%") (field (name "MANUFACTURER PART NO.") "WSK1206R0100FEA18"))
      (libsource (lib "Dahlia Carrier Board") (part "R-Vishay-WSK1206R0100FEA18"))
    )
    (comp (ref "R169")
      (value "0R")
      (footprint "T_RESC0603X30N")
      (description "Resistor 0 ohm 63mW 1% 0603")
      (fields (field (name "TOLERANCE") "1%"))
      (libsource (lib "Dahlia Carrier Board") (part "R-0R-63mW-1%-0603"))
    )
    (comp (ref "R170")
      (value "0R")
      (footprint "T_RESC0603X30N")
      (description "Resistor 0 ohm 63mW 1% 0603")
      (fields (field (name "TOLERANCE") "1%"))
      (libsource (lib "Dahlia Carrier Board") (part "R-0R-63mW-1%-0603"))
    )
    (comp (ref "R171")
      (value "0R")
      (footprint "T_RESC0603X30N")
      (description "Resistor 0 ohm 63mW 1% 0603")
      (fields (field (name "TOLERANCE") "1%"))
      (libsource (lib "Dahlia Carrier Board") (part "R-0R-63mW-1%-0603"))
    )
    (comp (ref "R173")
      (value "2.2K")
      (footprint "RESC1005X40N")
      (description "Resistor 2.2 Kohm 63mW 5% 0402")
      (fields (field (name "TOLERANCE") "5%"))
      (libsource (lib "Dahlia Carrier Board") (part "R-2.2K-63mW-5%-0402"))
    )
    (comp (ref "R175")
      (value "100K")
      (footprint "RESC1005X40N")
      (description "Resistor 100 Kohm 63mW 5% 0402")
      (fields (field (name "TOLERANCE") "5%"))
      (libsource (lib "Dahlia Carrier Board") (part "R-100K-63mW-5%-0402"))
    )
    (comp (ref "R176")
      (value "1K")
      (footprint "T_RESC0603X30N")
      (description "Resistor 1 Kohm 63mW 5% 0603")
      (fields (field (name "TOLERANCE") "5%"))
      (libsource (lib "Dahlia Carrier Board") (part "R-1K-63mW-5%-0603"))
    )
    (comp (ref "R177")
      (value "0R")
      (footprint "T_RESC0603X30N")
      (description "Resistor 0 ohm 63mW 1% 0603")
      (fields (field (name "TOLERANCE") "1%"))
      (libsource (lib "Dahlia Carrier Board") (part "R-0R-63mW-1%-0603"))
    )
    (comp (ref "R178")
      (value "100K")
      (footprint "RESC1005X40N")
      (description "Resistor 100 Kohm 63mW 5% 0402")
      (fields (field (name "TOLERANCE") "5%"))
      (libsource (lib "Dahlia Carrier Board") (part "R-100K-63mW-5%-0402"))
    )
    (comp (ref "R179")
      (value "1K")
      (footprint "RESC1005X40N")
      (description "Resistor 1 Kohm 63mW 5% 0402")
      (fields (field (name "TOLERANCE") "5%"))
      (libsource (lib "Dahlia Carrier Board") (part "R-1K-63mW-5%-0402"))
    )
    (comp (ref "R180")
      (value "0R")
      (footprint "T_RESC0603X30N")
      (description "Resistor 0 ohm 63mW 1% 0603")
      (fields (field (name "TOLERANCE") "1%"))
      (libsource (lib "Dahlia Carrier Board") (part "R-0R-63mW-1%-0603"))
    )
    (comp (ref "R181")
      (value "100K")
      (footprint "RESC1005X40N")
      (description "Resistor 100 Kohm 63mW 5% 0402")
      (fields (field (name "TOLERANCE") "5%"))
      (libsource (lib "Dahlia Carrier Board") (part "R-100K-63mW-5%-0402"))
    )
    (comp (ref "R182")
      (value "2.2K")
      (footprint "RESC1005X40N")
      (description "Resistor 2.2 Kohm 63mW 5% 0402")
      (fields (field (name "TOLERANCE") "5%"))
      (libsource (lib "Dahlia Carrier Board") (part "R-2.2K-63mW-5%-0402"))
    )
    (comp (ref "R183")
      (value "1K")
      (footprint "T_RESC0603X30N")
      (description "Resistor 1 Kohm 63mW 5% 0603")
      (fields (field (name "TOLERANCE") "5%"))
      (libsource (lib "Dahlia Carrier Board") (part "R-1K-63mW-5%-0603"))
    )
    (comp (ref "R184")
      (value "100K")
      (footprint "RESC1005X40N")
      (description "Resistor 100 Kohm 63mW 5% 0402")
      (fields (field (name "TOLERANCE") "5%"))
      (libsource (lib "Dahlia Carrier Board") (part "R-100K-63mW-5%-0402"))
    )
    (comp (ref "R185")
      (value "1K")
      (footprint "RESC1005X40N")
      (description "Resistor 1 Kohm 63mW 5% 0402")
      (fields (field (name "TOLERANCE") "5%"))
      (libsource (lib "Dahlia Carrier Board") (part "R-1K-63mW-5%-0402"))
    )
    (comp (ref "R186")
      (value "2.2K")
      (footprint "RESC1005X40N")
      (description "Resistor 2.2 Kohm 63mW 5% 0402")
      (fields (field (name "TOLERANCE") "5%"))
      (libsource (lib "Dahlia Carrier Board") (part "R-2.2K-63mW-5%-0402"))
    )
    (comp (ref "R187")
      (value "100K")
      (footprint "RESC1005X40N")
      (description "Resistor 100 Kohm 63mW 5% 0402")
      (fields (field (name "TOLERANCE") "5%"))
      (libsource (lib "Dahlia Carrier Board") (part "R-100K-63mW-5%-0402"))
    )
    (comp (ref "R188")
      (value "100K")
      (footprint "RESC1005X40N")
      (description "Resistor 100 Kohm 63mW 5% 0402")
      (fields (field (name "TOLERANCE") "5%"))
      (libsource (lib "Dahlia Carrier Board") (part "R-100K-63mW-5%-0402"))
    )
    (comp (ref "R189")
      (value "100K")
      (footprint "RESC1005X40N")
      (description "Resistor 100 Kohm 63mW 5% 0402")
      (fields (field (name "TOLERANCE") "5%"))
      (libsource (lib "Dahlia Carrier Board") (part "R-100K-63mW-5%-0402"))
    )
    (comp (ref "R190")
      (value "100K")
      (footprint "RESC1005X40N")
      (description "Resistor 100 Kohm 63mW 5% 0402")
      (fields (field (name "TOLERANCE") "5%"))
      (libsource (lib "Dahlia Carrier Board") (part "R-100K-63mW-5%-0402"))
    )
    (comp (ref "R191")
      (value "1K")
      (footprint "RESC1005X40N")
      (description "Resistor 1 Kohm 63mW 5% 0402")
      (fields (field (name "TOLERANCE") "5%"))
      (libsource (lib "Dahlia Carrier Board") (part "R-1K-63mW-5%-0402"))
    )
    (comp (ref "R192")
      (value "1K")
      (footprint "RESC1005X40N")
      (description "Resistor 1 Kohm 63mW 5% 0402")
      (fields (field (name "TOLERANCE") "5%"))
      (libsource (lib "Dahlia Carrier Board") (part "R-1K-63mW-5%-0402"))
    )
    (comp (ref "R193")
      (value "1M")
      (footprint "RESC3216X75N")
      (description "Resistor 1 Mohm 250mW 5% 1206")
      (fields (field (name "TOLERANCE") "5%"))
      (libsource (lib "Dahlia Carrier Board") (part "R-1M-250mW-5%-1206"))
    )
    (comp (ref "R194")
      (value "0R")
      (footprint "T_RESC0603X30N")
      (description "Resistor 0 ohm 63mW 1% 0603")
      (fields (field (name "TOLERANCE") "1%"))
      (libsource (lib "Dahlia Carrier Board") (part "R-0R-63mW-1%-0603"))
    )
    (comp (ref "R195")
      (value "0R")
      (footprint "T_RESC0603X30N")
      (description "Resistor 0 ohm 63mW 1% 0603")
      (fields (field (name "TOLERANCE") "1%"))
      (libsource (lib "Dahlia Carrier Board") (part "R-0R-63mW-1%-0603"))
    )
    (comp (ref "R196")
      (value "100K")
      (footprint "RESC1005X40N")
      (description "Resistor 100 Kohm 63mW 5% 0402")
      (fields (field (name "TOLERANCE") "5%"))
      (libsource (lib "Dahlia Carrier Board") (part "R-100K-63mW-5%-0402"))
    )
    (comp (ref "T8")
      (value "BSS138-7-F")
      (footprint "SOT95P237X112-3N")
      (description "N-channel MOSFET, BSS138-7-F")
      (fields (field (name "MANUFACTURER PART NO.") "BSS138-7-F"))
      (libsource (lib "Dahlia Carrier Board") (part "T-Diodes-BSS138-7-F"))
    )
    (comp (ref "T17")
      (value "NTMFS5C670NLT1G")
      (footprint "T_ONSemi_NTMFS5C670NLT1G")
      (description "MOSFET N-CH 60V 68A SO8FL")
      (fields (field (name "MANUFACTURER PART NO.") "NTMFS5C670NLT1G"))
      (libsource (lib "") (part "T-ONSemi-NTMFS5C670NLT1G_1"))
    )
    (comp (ref "T18")
      (value "NTMFS5C670NLT1G")
      (footprint "T_ONSemi_NTMFS5C670NLT1G")
      (description "MOSFET N-CH 60V 68A SO8FL")
      (fields (field (name "MANUFACTURER PART NO.") "NTMFS5C670NLT1G"))
      (libsource (lib "Dahlia Carrier Board") (part "T-ONSemi-NTMFS5C670NLT1G"))
    )
    (comp (ref "T19")
      (value "MMBT5551LT1G")
      (footprint "ONSC-SOT-23-3-318-08_V")
      (description "Bipolar Transistor NPN 160V 600mA  225mW Surface Mount SOT-23-3")
      (libsource (lib "Dahlia Carrier Board") (part "T-ONSemi-MMBT5551LT1G -SOT-23"))
    )
    (comp (ref "T20")
      (value "MMBT5551LT1G")
      (footprint "ONSC-SOT-23-3-318-08_V")
      (description "Bipolar Transistor NPN 160V 600mA  225mW Surface Mount SOT-23-3")
      (libsource (lib "Dahlia Carrier Board") (part "T-ONSemi-MMBT5551LT1G -SOT-23"))
    )
    (comp (ref "T21")
      (value "BSS138-7-F")
      (footprint "SOT95P237X112-3N")
      (description "N-channel MOSFET, BSS138-7-F")
      (fields (field (name "MANUFACTURER PART NO.") "BSS138-7-F"))
      (libsource (lib "Dahlia Carrier Board") (part "T-Diodes-BSS138-7-F"))
    )
    (comp (ref "T23")
      (value "BSS138-7-F")
      (footprint "SOT95P237X112-3N")
      (description "N-channel MOSFET, BSS138-7-F")
      (fields (field (name "MANUFACTURER PART NO.") "BSS138-7-F"))
      (libsource (lib "Dahlia Carrier Board") (part "T-Diodes-BSS138-7-F"))
    )
    (comp (ref "T25")
      (value "BSS138-7-F")
      (footprint "SOT95P237X112-3N")
      (description "N-channel MOSFET, BSS138-7-F")
      (fields (field (name "MANUFACTURER PART NO.") "BSS138-7-F"))
      (libsource (lib "Dahlia Carrier Board") (part "T-Diodes-BSS138-7-F"))
    )
    (comp (ref "T26")
      (value "BSS138-7-F")
      (footprint "SOT95P237X112-3N")
      (description "N-channel MOSFET, BSS138-7-F")
      (fields (field (name "MANUFACTURER PART NO.") "BSS138-7-F"))
      (libsource (lib "Dahlia Carrier Board") (part "T-Diodes-BSS138-7-F"))
    )
    (comp (ref "T27")
      (value "BSS138-7-F")
      (footprint "SOT95P237X112-3N")
      (description "N-channel MOSFET, BSS138-7-F")
      (fields (field (name "MANUFACTURER PART NO.") "BSS138-7-F"))
      (libsource (lib "Dahlia Carrier Board") (part "T-Diodes-BSS138-7-F"))
    )
    (comp (ref "T29")
      (value "T-ONSemi-NTZD3154NT1G")
      (footprint "SOTFL50P160X60-6N")
      (description "Dual N-Channel 20V (D-S)  MOSFET")
      (fields (field (name "MANUFACTURER PART NO.") "NTZD3154NT1G"))
      (libsource (lib "Dahlia Carrier Board") (part "T-ONSemi-NTZD3154NT1G"))
    )
    (comp (ref "TP4")
      (value "Testpin-THT")
      (footprint "T_TP-THT")
      (description "Testpin THT")
      (libsource (lib "Dahlia Carrier Board") (part "Testpin-THT"))
    )
    (comp (ref "TP5")
      (value "Testpin-THT")
      (footprint "T_TP-THT")
      (description "Testpin THT")
      (libsource (lib "Dahlia Carrier Board") (part "Testpin-THT"))
    )
    (comp (ref "TP6")
      (value "Testpin-THT")
      (footprint "T_TP-THT")
      (description "Testpin THT")
      (libsource (lib "Dahlia Carrier Board") (part "Testpin-THT"))
    )
    (comp (ref "TP7")
      (value "Testpin-THT")
      (footprint "T_TP-THT")
      (description "Testpin THT")
      (libsource (lib "Dahlia Carrier Board") (part "Testpin-THT"))
    )
    (comp (ref "TP8")
      (value "Testpin-THT")
      (footprint "T_TP-THT")
      (description "Testpin THT")
      (libsource (lib "Dahlia Carrier Board") (part "Testpin-THT"))
    )
    (comp (ref "TP10")
      (value "Testpin-THT")
      (footprint "T_TP-THT")
      (description "Testpin THT")
      (libsource (lib "Dahlia Carrier Board") (part "Testpin-THT"))
    )
    (comp (ref "TP11")
      (value "Testpin-THT")
      (footprint "T_TP-THT")
      (description "Testpin THT")
      (libsource (lib "Dahlia Carrier Board") (part "Testpin-THT"))
    )
    (comp (ref "TP12")
      (value "Testpin-THT")
      (footprint "T_TP-THT")
      (description "Testpin THT")
      (libsource (lib "Dahlia Carrier Board") (part "Testpin-THT"))
    )
    (comp (ref "TP19")
      (value "Testpin-THT")
      (footprint "T_TP-THT")
      (description "Testpin THT")
      (libsource (lib "Dahlia Carrier Board") (part "Testpin-THT"))
    )
    (comp (ref "TP20")
      (value "Testpin-THT")
      (footprint "T_TP-THT")
      (description "Testpin THT")
      (libsource (lib "Dahlia Carrier Board") (part "Testpin-THT"))
    )
    (comp (ref "X1")
      (value "2309409-2")
      (footprint "CON-TE-2309409-2-SOLDERABLE-STANDOFFS")
      (description "DDR4 SODIMM Socket, 260 pins, 5.2mm(H), 0.5mm Pitch")
      (libsource (lib "Dahlia Carrier Board") (part "CON-TE-2309409-2"))
    )
    (comp (ref "X6")
      (value "826936-5")
      (footprint "T_TYCO_826936-5")
      (description "Header, 5-Pin")
      (fields (field (name "MANUFACTURER PART NO.") "826936-5"))
      (libsource (lib "Dahlia Carrier Board") (part "CON-Tyco-826936-5-1X5-2.54mm"))
    )
    (comp (ref "X10")
      (value "12401598E4#2A")
      (footprint "CON-AMPHENOL-12401598E4#2A")
      (description "USB 3.1 Gen 2, Input Output Connectors, USB type C, Receptacle, Top mount, dual-row SMT, 1.6mmPCB")
      (fields (field (name "MANUFACTURER PART NO.") "12401598E4#2A"))
      (libsource (lib "") (part "CON-Amphenol-12401598E4#2A_1"))
    )
  )
  (nets
    (net (code "3") (name "+V1.8_SW") (class "Default")
      (node (ref "C107") (pin "2") (pinfunction "2_2") (pintype "passive"))
      (node (ref "C227") (pin "2") (pinfunction "2_2") (pintype "passive"))
      (node (ref "IC19") (pin "1") (pinfunction "VCCA_1") (pintype "power_in"))
      (node (ref "IC19") (pin "5") (pinfunction "OE_5") (pintype "input"))
      (node (ref "T29") (pin "5") (pinfunction "G_5") (pintype "passive"))
      (node (ref "X6") (pin "5") (pinfunction "5_5") (pintype "passive"))
    )
    (net (code "4") (name "+V3.3") (class "Default")
      (node (ref "R167") (pin "1") (pinfunction "1_1") (pintype "passive"))
      (node (ref "R185") (pin "1") (pinfunction "1_1") (pintype "passive"))
    )
    (net (code "5") (name "+V3.3_SW") (class "Default")
      (node (ref "C106") (pin "2") (pinfunction "2_2") (pintype "passive"))
      (node (ref "C116") (pin "2") (pinfunction "2_2") (pintype "passive"))
      (node (ref "C226") (pin "2") (pinfunction "2_2") (pintype "passive"))
      (node (ref "IC19") (pin "8") (pinfunction "VCCB_8") (pintype "power_in"))
      (node (ref "IC21") (pin "5") (pinfunction "VSS_5") (pintype "power_in"))
      (node (ref "R141") (pin "2") (pinfunction "2_2") (pintype "passive"))
      (node (ref "R142") (pin "2") (pinfunction "2_2") (pintype "passive"))
      (node (ref "R149") (pin "2") (pinfunction "2_2") (pintype "passive"))
      (node (ref "R153") (pin "2") (pinfunction "2_2") (pintype "passive"))
      (node (ref "R191") (pin "1") (pinfunction "1_1") (pintype "passive"))
      (node (ref "R192") (pin "1") (pinfunction "1_1") (pintype "passive"))
      (node (ref "X6") (pin "4") (pinfunction "4_4") (pintype "passive"))
    )
    (net (code "6") (name "+V5_PD") (class "Default")
      (node (ref "C111") (pin "2") (pinfunction "2_2") (pintype "passive"))
      (node (ref "C112") (pin "2") (pinfunction "2_2") (pintype "passive"))
      (node (ref "C132") (pin "2") (pinfunction "2_2") (pintype "passive"))
      (node (ref "IC24") (pin "3") (pinfunction "Vout_3") (pintype "passive"))
      (node (ref "LED10") (pin "A") (pinfunction "A_A") (pintype "passive"))
      (node (ref "R152") (pin "2") (pinfunction "2_2") (pintype "passive"))
      (node (ref "R154") (pin "2") (pinfunction "2_2") (pintype "passive"))
      (node (ref "R156") (pin "2") (pinfunction "2_2") (pintype "passive"))
      (node (ref "R166") (pin "2") (pinfunction "2_2") (pintype "passive"))
      (node (ref "R171") (pin "2") (pinfunction "2_2") (pintype "passive"))
      (node (ref "R173") (pin "1") (pinfunction "1_1") (pintype "passive"))
      (node (ref "R182") (pin "1") (pinfunction "1_1") (pintype "passive"))
      (node (ref "R77") (pin "1") (pinfunction "1_1") (pintype "passive"))
      (node (ref "R81") (pin "1") (pinfunction "1_1") (pintype "passive"))
    )
    (net (code "7") (name "+V5_SW") (class "Default")
      (node (ref "C225") (pin "2") (pinfunction "2_2") (pintype "passive"))
      (node (ref "R186") (pin "2") (pinfunction "2_2") (pintype "passive"))
      (node (ref "X6") (pin "3") (pinfunction "3_3") (pintype "passive"))
    )
    (net (code "8") (name "+VREG_1V2") (class "Default")
      (node (ref "C125") (pin "1") (pinfunction "1_1") (pintype "passive"))
      (node (ref "IC23") (pin "21") (pinfunction "VREG_1V2_21") (pintype "power_in"))
    )
    (net (code "9") (name "+VREG_2V7") (class "Default")
      (node (ref "C61") (pin "1") (pinfunction "1_1") (pintype "passive"))
      (node (ref "IC23") (pin "23") (pinfunction "VREG_2V7_23") (pintype "power_in"))
      (node (ref "R108") (pin "2") (pinfunction "2_2") (pintype "passive"))
      (node (ref "R184") (pin "2") (pinfunction "2_2") (pintype "passive"))
      (node (ref "R187") (pin "1") (pinfunction "1_1") (pintype "passive"))
      (node (ref "R188") (pin "1") (pinfunction "1_1") (pintype "passive"))
      (node (ref "R189") (pin "1") (pinfunction "1_1") (pintype "passive"))
      (node (ref "R194") (pin "2") (pinfunction "2_2") (pintype "passive"))
      (node (ref "R195") (pin "2") (pinfunction "2_2") (pintype "passive"))
    )
    (net (code "10") (name "+V_BUS_PD") (class "Default")
      (node (ref "C110") (pin "2") (pinfunction "2_2") (pintype "passive"))
      (node (ref "C114") (pin "2") (pinfunction "2_2") (pintype "passive"))
      (node (ref "C126") (pin "2") (pinfunction "2_2") (pintype "passive"))
      (node (ref "C131") (pin "2") (pinfunction "2_2") (pintype "passive"))
      (node (ref "D24") (pin "A") (pinfunction "A_A") (pintype "passive"))
      (node (ref "IC20") (pin "11") (pinfunction "VIN_11") (pintype "power_in"))
      (node (ref "IC20") (pin "12") (pinfunction "VIN_12") (pintype "power_in"))
      (node (ref "IC23") (pin "24") (pinfunction "VDD_24") (pintype "power_in"))
      (node (ref "IC24") (pin "1") (pinfunction "Vin_1") (pintype "passive"))
      (node (ref "L48") (pin "2") (pinfunction "2_2") (pintype "passive"))
      (node (ref "R175") (pin "2") (pinfunction "2_2") (pintype "passive"))
      (node (ref "R44") (pin "2") (pinfunction "2_2") (pintype "passive"))
    )
    (net (code "11") (name "+V_PWR_IN_1") (class "Default")
      (node (ref "C105") (pin "2") (pinfunction "2_2") (pintype "passive"))
      (node (ref "L20") (pin "1") (pinfunction "1_1") (pintype "passive"))
    )
    (net (code "12") (name "+V_SUPPLY_FILT") (class "Default")
      (node (ref "C113") (pin "1") (pinfunction "1_1") (pintype "passive"))
      (node (ref "C247") (pin "2") (pinfunction "2_2") (pintype "passive"))
      (node (ref "C248") (pin "2") (pinfunction "2_2") (pintype "passive"))
      (node (ref "C249") (pin "2") (pinfunction "2_2") (pintype "passive"))
      (node (ref "C250") (pin "2") (pinfunction "2_2") (pintype "passive"))
      (node (ref "C251") (pin "2") (pinfunction "2_2") (pintype "passive"))
      (node (ref "C252") (pin "2") (pinfunction "2_2") (pintype "passive"))
      (node (ref "C253") (pin "2") (pinfunction "2_2") (pintype "passive"))
      (node (ref "C254") (pin "2") (pinfunction "2_2") (pintype "passive"))
      (node (ref "C255") (pin "2") (pinfunction "2_2") (pintype "passive"))
      (node (ref "C256") (pin "2") (pinfunction "2_2") (pintype "passive"))
      (node (ref "C257") (pin "2") (pinfunction "2_2") (pintype "passive"))
      (node (ref "C258") (pin "2") (pinfunction "2_2") (pintype "passive"))
      (node (ref "C259") (pin "2") (pinfunction "2_2") (pintype "passive"))
      (node (ref "C260") (pin "2") (pinfunction "2_2") (pintype "passive"))
      (node (ref "C261") (pin "2") (pinfunction "2_2") (pintype "passive"))
      (node (ref "C262") (pin "2") (pinfunction "2_2") (pintype "passive"))
      (node (ref "C263") (pin "2") (pinfunction "2_2") (pintype "passive"))
      (node (ref "C264") (pin "2") (pinfunction "2_2") (pintype "passive"))
      (node (ref "IC20") (pin "1") (pinfunction "VOUT_1") (pintype "power_in"))
      (node (ref "IC20") (pin "2") (pinfunction "VOUT_2") (pintype "power_in"))
      (node (ref "R135") (pin "4") (pinfunction "4_4") (pintype "passive"))
      (node (ref "R183") (pin "2") (pinfunction "2_2") (pintype "passive"))
    )
    (net (code "13") (name "+V_SUPPLY_FILT_SW") (class "Default")
      (node (ref "X6") (pin "1") (pinfunction "1_1") (pintype "passive"))
    )
    (net (code "14") (name "/+V_BAT") (class "Default")
      (node (ref "BAT1") (pin "1") (pinfunction "+_1") (pintype "passive"))
      (node (ref "R179") (pin "2") (pinfunction "2_2") (pintype "passive"))
    )
    (net (code "15") (name "/+V_PWR_IN_2") (class "Default")
      (node (ref "C115") (pin "2") (pinfunction "2_2") (pintype "passive"))
      (node (ref "L48") (pin "1") (pinfunction "1_1") (pintype "passive"))
      (node (ref "X10") (pin "A4") (pinfunction "VBUS_A4") (pintype "passive"))
      (node (ref "X10") (pin "A9") (pinfunction "VBUS_A9") (pintype "passive"))
      (node (ref "X10") (pin "B4") (pinfunction "VBUS_B4") (pintype "passive"))
      (node (ref "X10") (pin "B9") (pinfunction "VBUS_B9") (pintype "passive"))
    )
    (net (code "16") (name "/FAULT") (class "Default")
      (node (ref "R184") (pin "1") (pinfunction "1_1") (pintype "passive"))
      (node (ref "T27") (pin "1") (pinfunction "G_1") (pintype "passive"))
      (node (ref "T8") (pin "3") (pinfunction "D_3") (pintype "passive"))
    )
    (net (code "18") (name "/I2C_1_SCL") (class "Default")
      (node (ref "R145") (pin "1") (pinfunction "1_1") (pintype "passive"))
      (node (ref "R177") (pin "1") (pinfunction "1_1") (pintype "passive"))
    )
    (net (code "19") (name "/I2C_1_SDA") (class "Default")
      (node (ref "R146") (pin "1") (pinfunction "1_1") (pintype "passive"))
      (node (ref "R180") (pin "1") (pinfunction "1_1") (pintype "passive"))
    )
    (net (code "20") (name "/PWR_IN_1_FILT") (class "Default")
      (node (ref "C95") (pin "2") (pinfunction "2_2") (pintype "passive"))
      (node (ref "IC18") (pin "1") (pinfunction "Vin_1") (pintype "passive"))
      (node (ref "L20") (pin "2") (pinfunction "2_2") (pintype "passive"))
      (node (ref "R134") (pin "2") (pinfunction "2_2") (pintype "passive"))
      (node (ref "R138") (pin "2") (pinfunction "2_2") (pintype "passive"))
      (node (ref "T17") (pin "5") (pinfunction "D_5") (pintype "passive"))
      (node (ref "T17") (pin "6") (pinfunction "D_6") (pintype "passive"))
      (node (ref "T17") (pin "7") (pinfunction "D_7") (pintype "passive"))
      (node (ref "T17") (pin "8") (pinfunction "D_8") (pintype "passive"))
    )
    (net (code "21") (name "/PWR_IN_2_CC1") (class "Default")
      (node (ref "C127") (pin "2") (pinfunction "2_2") (pintype "passive"))
      (node (ref "D26") (pin "2") (pinfunction "2_2") (pintype "power_in"))
      (node (ref "IC23") (pin "1") (pinfunction "CC1DB_1") (pintype "bidirectional"))
      (node (ref "IC23") (pin "2") (pinfunction "CC1_2") (pintype "bidirectional"))
      (node (ref "X10") (pin "A5") (pinfunction "CC1_A5") (pintype "passive"))
    )
    (net (code "22") (name "/PWR_IN_2_CC2") (class "Default")
      (node (ref "C128") (pin "2") (pinfunction "2_2") (pintype "passive"))
      (node (ref "D26") (pin "1") (pinfunction "1_1") (pintype "power_in"))
      (node (ref "IC23") (pin "4") (pinfunction "CC2_4") (pintype "bidirectional"))
      (node (ref "IC23") (pin "5") (pinfunction "CC2DB_5") (pintype "bidirectional"))
      (node (ref "X10") (pin "B5") (pinfunction "CC2_B5") (pintype "passive"))
    )
    (net (code "23") (name "/THERMAL") (class "Default")
      (node (ref "IC20") (pin "13") (pinfunction "EXP_13") (pintype "power_in+no_connect"))
    )
    (net (code "24") (name "/USB_CHG_CON_N") (class "Default")
      (node (ref "D33") (pin "1") (pinfunction "C_1") (pintype "power_in"))
      (node (ref "R161") (pin "2") (pinfunction "2_2") (pintype "passive"))
      (node (ref "X10") (pin "A7") (pinfunction "DN1_A7") (pintype "passive"))
      (node (ref "X10") (pin "B7") (pinfunction "DN2_B7") (pintype "passive"))
    )
    (net (code "25") (name "/USB_CHG_CON_P") (class "Default")
      (node (ref "D32") (pin "1") (pinfunction "C_1") (pintype "power_in"))
      (node (ref "R160") (pin "2") (pinfunction "2_2") (pintype "passive"))
      (node (ref "X10") (pin "A6") (pinfunction "DP1_A6") (pintype "passive"))
      (node (ref "X10") (pin "B6") (pinfunction "DP2_B6") (pintype "passive"))
    )
    (net (code "26") (name "/USB_CHG_N") (class "Default")
      (node (ref "IC22") (pin "8") (pinfunction "DM_CON_8") (pintype "passive"))
      (node (ref "R161") (pin "1") (pinfunction "1_1") (pintype "passive"))
    )
    (net (code "27") (name "/USB_CHG_P") (class "Default")
      (node (ref "IC22") (pin "7") (pinfunction "DP_CON_7") (pintype "passive"))
      (node (ref "R160") (pin "1") (pinfunction "1_1") (pintype "passive"))
    )
    (net (code "28") (name "/VBUS_EN_SNK") (class "Default")
      (node (ref "R166") (pin "1") (pinfunction "1_1") (pintype "passive"))
      (node (ref "T23") (pin "1") (pinfunction "G_1") (pintype "passive"))
      (node (ref "T25") (pin "1") (pinfunction "G_1") (pintype "passive"))
      (node (ref "T26") (pin "3") (pinfunction "D_3") (pintype "passive"))
    )
    (net (code "29") (name "/VCC") (class "Default")
      (node (ref "C118") (pin "2") (pinfunction "2_2") (pintype "passive"))
      (node (ref "C119") (pin "2") (pinfunction "2_2") (pintype "passive"))
      (node (ref "C120") (pin "2") (pinfunction "2_2") (pintype "passive"))
      (node (ref "C121") (pin "2") (pinfunction "2_2") (pintype "passive"))
      (node (ref "C122") (pin "2") (pinfunction "2_2") (pintype "passive"))
      (node (ref "C123") (pin "2") (pinfunction "2_2") (pintype "passive"))
      (node (ref "R167") (pin "4") (pinfunction "4_4") (pintype "passive"))
      (node (ref "TP12") (pin "1") (pinfunction "1_1") (pintype "passive"))
      (node (ref "X1") (pin "251") (pinfunction "VCC_251") (pintype "passive"))
      (node (ref "X1") (pin "253") (pinfunction "VCC_253") (pintype "passive"))
      (node (ref "X1") (pin "255") (pinfunction "VCC_255") (pintype "passive"))
      (node (ref "X1") (pin "257") (pinfunction "VCC_257") (pintype "passive"))
      (node (ref "X1") (pin "259") (pinfunction "VCC_259") (pintype "passive"))
    )
    (net (code "30") (name "/VCC_BACKUP") (class "Default")
      (node (ref "R179") (pin "1") (pinfunction "1_1") (pintype "passive"))
      (node (ref "X1") (pin "249") (pinfunction "VCC_BACKUP_249") (pintype "passive"))
    )
    (net (code "31") (name "GND") (class "Default")
      (node (ref "BAT1") (pin "2") (pinfunction "-_2") (pintype "passive"))
      (node (ref "C104") (pin "1") (pinfunction "1_1") (pintype "passive"))
      (node (ref "C105") (pin "1") (pinfunction "1_1") (pintype "passive"))
      (node (ref "C106") (pin "1") (pinfunction "1_1") (pintype "passive"))
      (node (ref "C107") (pin "1") (pinfunction "1_1") (pintype "passive"))
      (node (ref "C108") (pin "2") (pinfunction "2_2") (pintype "passive"))
      (node (ref "C110") (pin "1") (pinfunction "1_1") (pintype "passive"))
      (node (ref "C111") (pin "1") (pinfunction "1_1") (pintype "passive"))
      (node (ref "C112") (pin "1") (pinfunction "1_1") (pintype "passive"))
      (node (ref "C113") (pin "2") (pinfunction "2_2") (pintype "passive"))
      (node (ref "C114") (pin "1") (pinfunction "1_1") (pintype "passive"))
      (node (ref "C115") (pin "1") (pinfunction "1_1") (pintype "passive"))
      (node (ref "C116") (pin "1") (pinfunction "1_1") (pintype "passive"))
      (node (ref "C117") (pin "1") (pinfunction "1_1") (pintype "passive"))
      (node (ref "C118") (pin "1") (pinfunction "1_1") (pintype "passive"))
      (node (ref "C119") (pin "1") (pinfunction "1_1") (pintype "passive"))
      (node (ref "C120") (pin "1") (pinfunction "1_1") (pintype "passive"))
      (node (ref "C121") (pin "1") (pinfunction "1_1") (pintype "passive"))
      (node (ref "C122") (pin "1") (pinfunction "1_1") (pintype "passive"))
      (node (ref "C123") (pin "1") (pinfunction "1_1") (pintype "passive"))
      (node (ref "C124") (pin "1") (pinfunction "1_1") (pintype "passive"))
      (node (ref "C125") (pin "2") (pinfunction "2_2") (pintype "passive"))
      (node (ref "C126") (pin "1") (pinfunction "1_1") (pintype "passive"))
      (node (ref "C127") (pin "1") (pinfunction "1_1") (pintype "passive"))
      (node (ref "C128") (pin "1") (pinfunction "1_1") (pintype "passive"))
      (node (ref "C129") (pin "2") (pinfunction "2_2") (pintype "passive"))
      (node (ref "C130") (pin "1") (pinfunction "1_1") (pintype "passive"))
      (node (ref "C131") (pin "1") (pinfunction "1_1") (pintype "passive"))
      (node (ref "C132") (pin "1") (pinfunction "1_1") (pintype "passive"))
      (node (ref "C225") (pin "1") (pinfunction "1_1") (pintype "passive"))
      (node (ref "C226") (pin "1") (pinfunction "1_1") (pintype "passive"))
      (node (ref "C227") (pin "1") (pinfunction "1_1") (pintype "passive"))
      (node (ref "C247") (pin "1") (pinfunction "1_1") (pintype "passive"))
      (node (ref "C248") (pin "1") (pinfunction "1_1") (pintype "passive"))
      (node (ref "C249") (pin "1") (pinfunction "1_1") (pintype "passive"))
      (node (ref "C250") (pin "1") (pinfunction "1_1") (pintype "passive"))
      (node (ref "C251") (pin "1") (pinfunction "1_1") (pintype "passive"))
      (node (ref "C252") (pin "1") (pinfunction "1_1") (pintype "passive"))
      (node (ref "C253") (pin "1") (pinfunction "1_1") (pintype "passive"))
      (node (ref "C254") (pin "1") (pinfunction "1_1") (pintype "passive"))
      (node (ref "C255") (pin "1") (pinfunction "1_1") (pintype "passive"))
      (node (ref "C256") (pin "1") (pinfunction "1_1") (pintype "passive"))
      (node (ref "C257") (pin "1") (pinfunction "1_1") (pintype "passive"))
      (node (ref "C258") (pin "1") (pinfunction "1_1") (pintype "passive"))
      (node (ref "C259") (pin "1") (pinfunction "1_1") (pintype "passive"))
      (node (ref "C260") (pin "1") (pinfunction "1_1") (pintype "passive"))
      (node (ref "C261") (pin "1") (pinfunction "1_1") (pintype "passive"))
      (node (ref "C262") (pin "1") (pinfunction "1_1") (pintype "passive"))
      (node (ref "C263") (pin "1") (pinfunction "1_1") (pintype "passive"))
      (node (ref "C264") (pin "1") (pinfunction "1_1") (pintype "passive"))
      (node (ref "C61") (pin "2") (pinfunction "2_2") (pintype "passive"))
      (node (ref "C95") (pin "1") (pinfunction "1_1") (pintype "passive"))
      (node (ref "D26") (pin "3") (pinfunction "3_3") (pintype "power_in"))
      (node (ref "D32") (pin "2") (pinfunction "A_2") (pintype "power_in"))
      (node (ref "D33") (pin "2") (pinfunction "A_2") (pintype "power_in"))
      (node (ref "IC18") (pin "11") (pinfunction "GND-PAD_11") (pintype "passive"))
      (node (ref "IC18") (pin "5") (pinfunction "GND_5") (pintype "passive"))
      (node (ref "IC19") (pin "4") (pinfunction "GND_4") (pintype "power_in"))
      (node (ref "IC20") (pin "6") (pinfunction "GND_6") (pintype "power_in"))
      (node (ref "IC21") (pin "6") (pinfunction "GND_6") (pintype "power_in"))
      (node (ref "IC22") (pin "6") (pinfunction "GND_6") (pintype "passive"))
      (node (ref "IC23") (pin "10") (pinfunction "GND_10") (pintype "power_in"))
      (node (ref "IC23") (pin "25") (pinfunction "EP_25") (pintype "power_in"))
      (node (ref "IC24") (pin "2") (pinfunction "GND_2") (pintype "passive"))
      (node (ref "IC24") (pin "4") (pinfunction "GND_4") (pintype "passive"))
      (node (ref "JP4") (pin "3") (pinfunction "3_3") (pintype "passive"))
      (node (ref "LED11") (pin "K") (pinfunction "K_K") (pintype "passive"))
      (node (ref "LED14") (pin "K") (pinfunction "K_K") (pintype "passive"))
      (node (ref "LED15") (pin "K") (pinfunction "K_K") (pintype "passive"))
      (node (ref "LED16") (pin "K") (pinfunction "K_K") (pintype "passive"))
      (node (ref "R144") (pin "1") (pinfunction "1_1") (pintype "passive"))
      (node (ref "R150") (pin "2") (pinfunction "2_2") (pintype "passive"))
      (node (ref "R155") (pin "2") (pinfunction "2_2") (pintype "passive"))
      (node (ref "R163") (pin "1") (pinfunction "1_1") (pintype "passive"))
      (node (ref "R165") (pin "1") (pinfunction "1_1") (pintype "passive"))
      (node (ref "R169") (pin "1") (pinfunction "1_1") (pintype "passive"))
      (node (ref "R170") (pin "1") (pinfunction "1_1") (pintype "passive"))
      (node (ref "R178") (pin "1") (pinfunction "1_1") (pintype "passive"))
      (node (ref "R181") (pin "1") (pinfunction "1_1") (pintype "passive"))
      (node (ref "R190") (pin "2") (pinfunction "2_2") (pintype "passive"))
      (node (ref "R193") (pin "1") (pinfunction "1_1") (pintype "passive"))
      (node (ref "R196") (pin "1") (pinfunction "1_1") (pintype "passive"))
      (node (ref "T21") (pin "2") (pinfunction "S_2") (pintype "passive"))
      (node (ref "T23") (pin "2") (pinfunction "S_2") (pintype "passive"))
      (node (ref "T25") (pin "2") (pinfunction "S_2") (pintype "passive"))
      (node (ref "T26") (pin "2") (pinfunction "S_2") (pintype "passive"))
      (node (ref "T27") (pin "2") (pinfunction "S_2") (pintype "passive"))
      (node (ref "T29") (pin "1") (pinfunction "S_1") (pintype "passive"))
      (node (ref "T29") (pin "2") (pinfunction "G_2") (pintype "passive"))
      (node (ref "T29") (pin "4") (pinfunction "S_4") (pintype "passive"))
      (node (ref "T8") (pin "2") (pinfunction "S_2") (pintype "passive"))
      (node (ref "X1") (pin "10") (pinfunction "GND_10") (pintype "passive"))
      (node (ref "X1") (pin "103") (pinfunction "GND_103") (pintype "passive"))
      (node (ref "X1") (pin "109") (pinfunction "GND_109") (pintype "passive"))
      (node (ref "X1") (pin "11") (pinfunction "GND_11") (pintype "passive"))
      (node (ref "X1") (pin "110") (pinfunction "GND_110") (pintype "passive"))
      (node (ref "X1") (pin "115") (pinfunction "GND_115") (pintype "passive"))
      (node (ref "X1") (pin "121") (pinfunction "GND_121") (pintype "passive"))
      (node (ref "X1") (pin "122") (pinfunction "GND_122") (pintype "passive"))
      (node (ref "X1") (pin "127") (pinfunction "GND_127") (pintype "passive"))
      (node (ref "X1") (pin "134") (pinfunction "GND_134") (pintype "passive"))
      (node (ref "X1") (pin "145") (pinfunction "GND_145") (pintype "passive"))
      (node (ref "X1") (pin "146") (pinfunction "GND_146") (pintype "passive"))
      (node (ref "X1") (pin "158") (pinfunction "GND_158") (pintype "passive"))
      (node (ref "X1") (pin "167") (pinfunction "GND_167") (pintype "passive"))
      (node (ref "X1") (pin "170") (pinfunction "GND_170") (pintype "passive"))
      (node (ref "X1") (pin "173") (pinfunction "GND_173") (pintype "passive"))
      (node (ref "X1") (pin "179") (pinfunction "GND_179") (pintype "passive"))
      (node (ref "X1") (pin "18") (pinfunction "GND_18") (pintype "passive"))
      (node (ref "X1") (pin "182") (pinfunction "GND_182") (pintype "passive"))
      (node (ref "X1") (pin "194") (pinfunction "GND_194") (pintype "passive"))
      (node (ref "X1") (pin "195") (pinfunction "GND_195") (pintype "passive"))
      (node (ref "X1") (pin "204") (pinfunction "GND_204") (pintype "passive"))
      (node (ref "X1") (pin "209") (pinfunction "GND_209") (pintype "passive"))
      (node (ref "X1") (pin "223") (pinfunction "GND_223") (pintype "passive"))
      (node (ref "X1") (pin "224") (pinfunction "GND_224") (pintype "passive"))
      (node (ref "X1") (pin "229") (pinfunction "GND_229") (pintype "passive"))
      (node (ref "X1") (pin "230") (pinfunction "GND_230") (pintype "passive"))
      (node (ref "X1") (pin "236") (pinfunction "GND_236") (pintype "passive"))
      (node (ref "X1") (pin "242") (pinfunction "GND_242") (pintype "passive"))
      (node (ref "X1") (pin "243") (pinfunction "GND_243") (pintype "passive"))
      (node (ref "X1") (pin "27") (pinfunction "GND_27") (pintype "passive"))
      (node (ref "X1") (pin "28") (pinfunction "GND_28") (pintype "passive"))
      (node (ref "X1") (pin "33") (pinfunction "GND_33") (pintype "passive"))
      (node (ref "X1") (pin "39") (pinfunction "GND_39") (pintype "passive"))
      (node (ref "X1") (pin "40") (pinfunction "GND_40") (pintype "passive"))
      (node (ref "X1") (pin "45") (pinfunction "GND_45") (pintype "passive"))
      (node (ref "X1") (pin "50") (pinfunction "GND_50") (pintype "passive"))
      (node (ref "X1") (pin "51") (pinfunction "GND_51") (pintype "passive"))
      (node (ref "X1") (pin "65") (pinfunction "GND_65") (pintype "passive"))
      (node (ref "X1") (pin "68") (pinfunction "GND_68") (pintype "passive"))
      (node (ref "X1") (pin "71") (pinfunction "GND_71") (pintype "passive"))
      (node (ref "X1") (pin "77") (pinfunction "GND_77") (pintype "passive"))
      (node (ref "X1") (pin "83") (pinfunction "GND_83") (pintype "passive"))
      (node (ref "X1") (pin "86") (pinfunction "GND_86") (pintype "passive"))
      (node (ref "X1") (pin "89") (pinfunction "GND_89") (pintype "passive"))
      (node (ref "X1") (pin "97") (pinfunction "GND_97") (pintype "passive"))
      (node (ref "X1") (pin "98") (pinfunction "GND_98") (pintype "passive"))
      (node (ref "X10") (pin "A1") (pinfunction "GND_A1") (pintype "passive"))
      (node (ref "X10") (pin "A12") (pinfunction "GND_A12") (pintype "passive"))
      (node (ref "X10") (pin "B1") (pinfunction "GND_B1") (pintype "passive"))
      (node (ref "X10") (pin "B12") (pinfunction "GND_B12") (pintype "passive"))
      (node (ref "X6") (pin "2") (pinfunction "2_2") (pintype "passive"))
    )
    (net (code "32") (name "GND_CHASSIS") (class "Default")
      (node (ref "C130") (pin "2") (pinfunction "2_2") (pintype "passive"))
      (node (ref "R193") (pin "2") (pinfunction "2_2") (pintype "passive"))
      (node (ref "X10") (pin "SH1") (pinfunction "SHIELD_SH1") (pintype "passive"))
      (node (ref "X10") (pin "SH2") (pinfunction "SHIELD_SH2") (pintype "passive"))
      (node (ref "X10") (pin "SH3") (pinfunction "SHIELD_SH3") (pintype "passive"))
      (node (ref "X10") (pin "SH4") (pinfunction "SHIELD_SH4") (pintype "passive"))
    )
    (net (code "33") (name "Net-(C104-Pad2)") (class "Default")
      (node (ref "C104") (pin "2") (pinfunction "2_2") (pintype "passive"))
      (node (ref "R136") (pin "1") (pinfunction "1_1") (pintype "passive"))
    )
    (net (code "34") (name "Net-(C108-Pad1)") (class "Default")
      (node (ref "C108") (pin "1") (pinfunction "1_1") (pintype "passive"))
      (node (ref "JP4") (pin "1") (pinfunction "1_1") (pintype "passive"))
    )
    (net (code "35") (name "Net-(C129-Pad1)") (class "Default")
      (node (ref "C129") (pin "1") (pinfunction "1_1") (pintype "passive"))
      (node (ref "D24") (pin "C") (pinfunction "C_C") (pintype "passive"))
      (node (ref "R44") (pin "1") (pinfunction "1_1") (pintype "passive"))
      (node (ref "R48") (pin "2") (pinfunction "2_2") (pintype "passive"))
    )
    (net (code "36") (name "Net-(D30-PadA)") (class "Default")
      (node (ref "D30") (pin "A") (pinfunction "A_A") (pintype "passive"))
      (node (ref "R134") (pin "1") (pinfunction "1_1") (pintype "passive"))
    )
    (net (code "37") (name "Net-(D31-A)") (class "Default")
      (node (ref "D31") (pin "2") (pinfunction "A_2") (pintype "power_in"))
      (node (ref "T17") (pin "1") (pinfunction "S_1") (pintype "passive"))
      (node (ref "T17") (pin "2") (pinfunction "S_2") (pintype "passive"))
      (node (ref "T17") (pin "3") (pinfunction "S_3") (pintype "passive"))
      (node (ref "T18") (pin "1") (pinfunction "S_1") (pintype "passive"))
      (node (ref "T18") (pin "2") (pinfunction "S_2") (pintype "passive"))
      (node (ref "T18") (pin "3") (pinfunction "S_3") (pintype "passive"))
    )
    (net (code "38") (name "Net-(D31-C)") (class "Default")
      (node (ref "D31") (pin "1") (pinfunction "C_1") (pintype "power_in"))
      (node (ref "IC18") (pin "10") (pinfunction "GATE_10") (pintype "passive"))
      (node (ref "R136") (pin "2") (pinfunction "2_2") (pintype "passive"))
      (node (ref "T17") (pin "4") (pinfunction "G_4") (pintype "passive"))
      (node (ref "T18") (pin "4") (pinfunction "G_4") (pintype "passive"))
    )
    (net (code "39") (name "Net-(IC18-OV)") (class "Default")
      (node (ref "IC18") (pin "3") (pinfunction "OV_3") (pintype "passive"))
      (node (ref "R143") (pin "1") (pinfunction "1_1") (pintype "passive"))
      (node (ref "R144") (pin "2") (pinfunction "2_2") (pintype "passive"))
    )
    (net (code "40") (name "Net-(IC18-RETRY)") (class "Default")
      (node (ref "IC18") (pin "4") (pinfunction "RETRY_4") (pintype "passive"))
      (node (ref "JP4") (pin "2") (pinfunction "2_2") (pintype "passive"))
    )
    (net (code "41") (name "Net-(IC18-SENSE)") (class "Default")
      (node (ref "IC18") (pin "9") (pinfunction "SENSE_9") (pintype "passive"))
      (node (ref "R135") (pin "2") (pinfunction "2_2") (pintype "passive"))
    )
    (net (code "42") (name "Net-(IC18-UV)") (class "Default")
      (node (ref "IC18") (pin "2") (pinfunction "UV_2") (pintype "passive"))
      (node (ref "R140") (pin "1") (pinfunction "1_1") (pintype "passive"))
      (node (ref "R143") (pin "2") (pinfunction "2_2") (pintype "passive"))
    )
    (net (code "43") (name "Net-(IC18-Vout)") (class "Default")
      (node (ref "IC18") (pin "8") (pinfunction "Vout_8") (pintype "passive"))
      (node (ref "R135") (pin "3") (pinfunction "3_3") (pintype "passive"))
    )
    (net (code "44") (name "Net-(IC18-~{FAULT})") (class "Default")
      (node (ref "IC18") (pin "7") (pinfunction "~{FAULT}_7") (pintype "passive"))
      (node (ref "LED8") (pin "K") (pinfunction "K_K") (pintype "passive"))
    )
    (net (code "45") (name "Net-(IC18-~{SHDN})") (class "Default")
      (node (ref "IC18") (pin "6") (pinfunction "~{SHDN}_6") (pintype "passive"))
      (node (ref "R138") (pin "1") (pinfunction "1_1") (pintype "passive"))
      (node (ref "R140") (pin "2") (pinfunction "2_2") (pintype "passive"))
    )
    (net (code "46") (name "Net-(IC19-A0)") (class "Default")
      (node (ref "IC19") (pin "2") (pinfunction "A0_2") (pintype "bidirectional"))
      (node (ref "R145") (pin "2") (pinfunction "2_2") (pintype "passive"))
    )
    (net (code "47") (name "Net-(IC19-A1)") (class "Default")
      (node (ref "IC19") (pin "3") (pinfunction "A1_3") (pintype "bidirectional"))
      (node (ref "R146") (pin "2") (pinfunction "2_2") (pintype "passive"))
    )
    (net (code "48") (name "Net-(IC19-B0)") (class "Default")
      (node (ref "IC19") (pin "7") (pinfunction "B0_7") (pintype "bidirectional"))
      (node (ref "IC21") (pin "4") (pinfunction "SCL_4") (pintype "input"))
      (node (ref "R141") (pin "1") (pinfunction "1_1") (pintype "passive"))
    )
    (net (code "49") (name "Net-(IC19-B1)") (class "Default")
      (node (ref "IC19") (pin "6") (pinfunction "B1_6") (pintype "bidirectional"))
      (node (ref "IC21") (pin "3") (pinfunction "SDA_3") (pintype "bidirectional"))
      (node (ref "R142") (pin "1") (pinfunction "1_1") (pintype "passive"))
    )
    (net (code "50") (name "Net-(IC20-ENB)") (class "Default")
      (node (ref "IC20") (pin "5") (pinfunction "ENB_5") (pintype "power_in"))
      (node (ref "R152") (pin "1") (pinfunction "1_1") (pintype "passive"))
      (node (ref "T21") (pin "3") (pinfunction "D_3") (pintype "passive"))
      (node (ref "T23") (pin "3") (pinfunction "D_3") (pintype "passive"))
    )
    (net (code "51") (name "Net-(IC20-FLTB)") (class "Default")
      (node (ref "IC20") (pin "4") (pinfunction "FLTB_4") (pintype "power_in"))
      (node (ref "R159") (pin "2") (pinfunction "2_2") (pintype "passive"))
    )
    (net (code "52") (name "Net-(IC20-POVP)") (class "Default")
      (node (ref "IC20") (pin "3") (pinfunction "POVP_3") (pintype "power_in"))
      (node (ref "R165") (pin "2") (pinfunction "2_2") (pintype "passive"))
    )
    (net (code "53") (name "Net-(IC20-SS)") (class "Default")
      (node (ref "C117") (pin "2") (pinfunction "2_2") (pintype "passive"))
      (node (ref "IC20") (pin "7") (pinfunction "SS_7") (pintype "power_in"))
    )
    (net (code "54") (name "Net-(IC21-A0)") (class "Default")
      (node (ref "IC21") (pin "2") (pinfunction "A0_2") (pintype "input"))
      (node (ref "R149") (pin "1") (pinfunction "1_1") (pintype "passive"))
      (node (ref "R150") (pin "1") (pinfunction "1_1") (pintype "passive"))
    )
    (net (code "55") (name "Net-(IC21-A1)") (class "Default")
      (node (ref "IC21") (pin "1") (pinfunction "A1_1") (pintype "input"))
      (node (ref "R153") (pin "1") (pinfunction "1_1") (pintype "passive"))
      (node (ref "R155") (pin "1") (pinfunction "1_1") (pintype "passive"))
    )
    (net (code "56") (name "Net-(IC21-VIN+)") (class "Default")
      (node (ref "C109") (pin "2") (pinfunction "2_2") (pintype "passive"))
      (node (ref "IC21") (pin "8") (pinfunction "VIN+_8") (pintype "input"))
      (node (ref "R157") (pin "2") (pinfunction "2_2") (pintype "passive"))
    )
    (net (code "57") (name "Net-(IC21-VIN-)") (class "Default")
      (node (ref "C109") (pin "1") (pinfunction "1_1") (pintype "passive"))
      (node (ref "IC21") (pin "7") (pinfunction "VIN-_7") (pintype "input"))
      (node (ref "R158") (pin "2") (pinfunction "2_2") (pintype "passive"))
    )
    (net (code "58") (name "Net-(IC22-CHG_DET)") (class "Default")
      (node (ref "IC22") (pin "10") (pinfunction "CHG_DET_10") (pintype "passive"))
      (node (ref "R162") (pin "1") (pinfunction "1_1") (pintype "passive"))
      (node (ref "R164") (pin "2") (pinfunction "2_2") (pintype "passive"))
    )
    (net (code "59") (name "Net-(IC22-DM_HOST)") (class "Default")
      (node (ref "IC22") (pin "2") (pinfunction "DM_HOST_2") (pintype "passive"))
      (node (ref "TP19") (pin "1") (pinfunction "1_1") (pintype "passive"))
    )
    (net (code "60") (name "Net-(IC22-DP_HOST)") (class "Default")
      (node (ref "IC22") (pin "3") (pinfunction "DP_HOST_3") (pintype "passive"))
      (node (ref "TP20") (pin "1") (pinfunction "1_1") (pintype "passive"))
    )
    (net (code "61") (name "Net-(IC22-GOOD_BAT)") (class "Default")
      (node (ref "IC22") (pin "5") (pinfunction "GOOD_BAT_5") (pintype "passive"))
      (node (ref "R156") (pin "1") (pinfunction "1_1") (pintype "passive"))
    )
    (net (code "62") (name "Net-(IC22-VBUS)") (class "Default")
      (node (ref "IC22") (pin "9") (pinfunction "VBUS_9") (pintype "passive"))
      (node (ref "R154") (pin "1") (pinfunction "1_1") (pintype "passive"))
    )
    (net (code "63") (name "Net-(IC23-ADDR0)") (class "Default")
      (node (ref "IC23") (pin "12") (pinfunction "ADDR0_12") (pintype "input"))
      (node (ref "R181") (pin "2") (pinfunction "2_2") (pintype "passive"))
      (node (ref "R195") (pin "1") (pinfunction "1_1") (pintype "passive"))
    )
    (net (code "64") (name "Net-(IC23-ADDR1)") (class "Default")
      (node (ref "IC23") (pin "13") (pinfunction "ADDR1_13") (pintype "input"))
      (node (ref "R194") (pin "1") (pinfunction "1_1") (pintype "passive"))
      (node (ref "R196") (pin "2") (pinfunction "2_2") (pintype "passive"))
    )
    (net (code "65") (name "Net-(IC23-ATTACH#)") (class "Default")
      (node (ref "IC23") (pin "11") (pinfunction "ATTACH#_11") (pintype "open_collector"))
      (node (ref "R189") (pin "2") (pinfunction "2_2") (pintype "passive"))
      (node (ref "TP6") (pin "1") (pinfunction "1_1") (pintype "passive"))
    )
    (net (code "66") (name "Net-(IC23-DISCH)") (class "Default")
      (node (ref "IC23") (pin "9") (pinfunction "DISCH_9") (pintype "open_collector"))
      (node (ref "R183") (pin "1") (pinfunction "1_1") (pintype "passive"))
    )
    (net (code "67") (name "Net-(IC23-GPIO)") (class "Default")
      (node (ref "IC23") (pin "15") (pinfunction "GPIO_15") (pintype "open_collector"))
      (node (ref "R108") (pin "1") (pinfunction "1_1") (pintype "passive"))
      (node (ref "T8") (pin "1") (pinfunction "G_1") (pintype "passive"))
    )
    (net (code "68") (name "Net-(IC23-NC)") (class "Default")
      (node (ref "IC23") (pin "3") (pinfunction "NC_3") (pintype "passive"))
      (node (ref "R170") (pin "2") (pinfunction "2_2") (pintype "passive"))
    )
    (net (code "69") (name "Net-(IC23-POWER_OK2#)") (class "Default")
      (node (ref "IC23") (pin "20") (pinfunction "POWER_OK2#_20") (pintype "open_collector"))
      (node (ref "LED22") (pin "K") (pinfunction "K_K") (pintype "passive"))
      (node (ref "R187") (pin "2") (pinfunction "2_2") (pintype "passive"))
      (node (ref "TP4") (pin "1") (pinfunction "1_1") (pintype "passive"))
    )
    (net (code "70") (name "Net-(IC23-POWER_OK3#)") (class "Default")
      (node (ref "IC23") (pin "14") (pinfunction "POWER_OK3#_14") (pintype "open_collector"))
      (node (ref "LED29") (pin "K") (pinfunction "K_K") (pintype "passive"))
      (node (ref "R188") (pin "2") (pinfunction "2_2") (pintype "passive"))
      (node (ref "TP5") (pin "1") (pinfunction "1_1") (pintype "passive"))
    )
    (net (code "71") (name "Net-(IC23-RESET)") (class "Default")
      (node (ref "IC23") (pin "6") (pinfunction "RESET_6") (pintype "input"))
      (node (ref "R190") (pin "1") (pinfunction "1_1") (pintype "passive"))
    )
    (net (code "72") (name "Net-(IC23-SCL)") (class "Default")
      (node (ref "IC23") (pin "7") (pinfunction "SCL_7") (pintype "input"))
      (node (ref "R177") (pin "2") (pinfunction "2_2") (pintype "passive"))
      (node (ref "TP7") (pin "1") (pinfunction "1_1") (pintype "passive"))
    )
    (net (code "73") (name "Net-(IC23-SDA)") (class "Default")
      (node (ref "IC23") (pin "8") (pinfunction "SDA_8") (pintype "open_collector"))
      (node (ref "R180") (pin "2") (pinfunction "2_2") (pintype "passive"))
      (node (ref "TP8") (pin "1") (pinfunction "1_1") (pintype "passive"))
    )
    (net (code "74") (name "Net-(IC23-VBUS_EN_SNK#)") (class "Default")
      (node (ref "IC23") (pin "16") (pinfunction "VBUS_EN_SNK#_16") (pintype "open_collector"))
      (node (ref "R176") (pin "2") (pinfunction "2_2") (pintype "passive"))
    )
    (net (code "75") (name "Net-(IC23-VBUS_VS_DISCH)") (class "Default")
      (node (ref "IC23") (pin "18") (pinfunction "VBUS_VS_DISCH_18") (pintype "input"))
      (node (ref "R48") (pin "1") (pinfunction "1_1") (pintype "passive"))
    )
    (net (code "76") (name "Net-(IC23-VSYS)") (class "Default")
      (node (ref "C124") (pin "2") (pinfunction "2_2") (pintype "passive"))
      (node (ref "IC23") (pin "22") (pinfunction "VSYS_22") (pintype "power_in"))
      (node (ref "R169") (pin "2") (pinfunction "2_2") (pintype "passive"))
      (node (ref "R171") (pin "1") (pinfunction "1_1") (pintype "passive"))
    )
    (net (code "77") (name "Net-(LED10-PadK)") (class "Default")
      (node (ref "LED10") (pin "K") (pinfunction "K_K") (pintype "passive"))
      (node (ref "R159") (pin "1") (pinfunction "1_1") (pintype "passive"))
    )
    (net (code "78") (name "Net-(LED11-PadA)") (class "Default")
      (node (ref "LED11") (pin "A") (pinfunction "A_A") (pintype "passive"))
      (node (ref "R164") (pin "1") (pinfunction "1_1") (pintype "passive"))
    )
    (net (code "79") (name "Net-(LED12-PadA)") (class "Default")
      (node (ref "LED12") (pin "A") (pinfunction "A_A") (pintype "passive"))
      (node (ref "R173") (pin "2") (pinfunction "2_2") (pintype "passive"))
    )
    (net (code "80") (name "Net-(LED13-PadA)") (class "Default")
      (node (ref "LED13") (pin "A") (pinfunction "A_A") (pintype "passive"))
      (node (ref "R182") (pin "2") (pinfunction "2_2") (pintype "passive"))
    )
    (net (code "81") (name "Net-(LED14-PadA)") (class "Default")
      (node (ref "LED14") (pin "A") (pinfunction "A_A") (pintype "passive"))
      (node (ref "R185") (pin "2") (pinfunction "2_2") (pintype "passive"))
    )
    (net (code "82") (name "Net-(LED15-PadA)") (class "Default")
      (node (ref "LED15") (pin "A") (pinfunction "A_A") (pintype "passive"))
      (node (ref "R186") (pin "1") (pinfunction "1_1") (pintype "passive"))
    )
    (net (code "83") (name "Net-(LED16-PadA)") (class "Default")
      (node (ref "LED16") (pin "A") (pinfunction "A_A") (pintype "passive"))
      (node (ref "R191") (pin "2") (pinfunction "2_2") (pintype "passive"))
    )
    (net (code "84") (name "Net-(LED17-PadA)") (class "Default")
      (node (ref "LED17") (pin "A") (pinfunction "A_A") (pintype "passive"))
      (node (ref "R192") (pin "2") (pinfunction "2_2") (pintype "passive"))
    )
    (net (code "85") (name "Net-(LED22-PadA)") (class "Default")
      (node (ref "LED22") (pin "A") (pinfunction "A_A") (pintype "passive"))
      (node (ref "R77") (pin "2") (pinfunction "2_2") (pintype "passive"))
    )
    (net (code "86") (name "Net-(LED29-PadA)") (class "Default")
      (node (ref "LED29") (pin "A") (pinfunction "A_A") (pintype "passive"))
      (node (ref "R81") (pin "2") (pinfunction "2_2") (pintype "passive"))
    )
    (net (code "87") (name "Net-(R135-Pad1)") (class "Default")
      (node (ref "R135") (pin "1") (pinfunction "1_1") (pintype "passive"))
      (node (ref "T18") (pin "5") (pinfunction "D_5") (pintype "passive"))
      (node (ref "T18") (pin "6") (pinfunction "D_6") (pintype "passive"))
      (node (ref "T18") (pin "7") (pinfunction "D_7") (pintype "passive"))
      (node (ref "T18") (pin "8") (pinfunction "D_8") (pintype "passive"))
    )
    (net (code "88") (name "Net-(R157-Pad1)") (class "Default")
      (node (ref "R157") (pin "1") (pinfunction "1_1") (pintype "passive"))
      (node (ref "R167") (pin "2") (pinfunction "2_2") (pintype "passive"))
      (node (ref "TP10") (pin "1") (pinfunction "1_1") (pintype "passive"))
    )
    (net (code "89") (name "Net-(R158-Pad1)") (class "Default")
      (node (ref "R158") (pin "1") (pinfunction "1_1") (pintype "passive"))
      (node (ref "R167") (pin "3") (pinfunction "3_3") (pintype "passive"))
      (node (ref "TP11") (pin "1") (pinfunction "1_1") (pintype "passive"))
    )
    (net (code "90") (name "Net-(T19-B)") (class "Default")
      (node (ref "R137") (pin "1") (pinfunction "1_1") (pintype "passive"))
      (node (ref "T19") (pin "1") (pinfunction "B_1") (pintype "passive"))
      (node (ref "T20") (pin "3") (pinfunction "C_3") (pintype "passive"))
    )
    (net (code "91") (name "Net-(T19-C)") (class "Default")
      (node (ref "D30") (pin "C") (pinfunction "C_C") (pintype "passive"))
      (node (ref "R137") (pin "2") (pinfunction "2_2") (pintype "passive"))
      (node (ref "T19") (pin "3") (pinfunction "C_3") (pintype "passive"))
    )
    (net (code "92") (name "Net-(T19-E)") (class "Default")
      (node (ref "R139") (pin "2") (pinfunction "2_2") (pintype "passive"))
      (node (ref "T19") (pin "2") (pinfunction "E_2") (pintype "passive"))
      (node (ref "T20") (pin "1") (pinfunction "B_1") (pintype "passive"))
    )
    (net (code "93") (name "Net-(T20-E)") (class "Default")
      (node (ref "LED8") (pin "A") (pinfunction "A_A") (pintype "passive"))
      (node (ref "R139") (pin "1") (pinfunction "1_1") (pintype "passive"))
      (node (ref "T20") (pin "2") (pinfunction "E_2") (pintype "passive"))
    )
    (net (code "94") (name "Net-(T21-G)") (class "Default")
      (node (ref "R162") (pin "2") (pinfunction "2_2") (pintype "passive"))
      (node (ref "R163") (pin "2") (pinfunction "2_2") (pintype "passive"))
      (node (ref "T21") (pin "1") (pinfunction "G_1") (pintype "passive"))
    )
    (net (code "95") (name "Net-(T25-D)") (class "Default")
      (node (ref "LED12") (pin "K") (pinfunction "K_K") (pintype "passive"))
      (node (ref "T25") (pin "3") (pinfunction "D_3") (pintype "passive"))
    )
    (net (code "96") (name "Net-(T26-G)") (class "Default")
      (node (ref "R175") (pin "1") (pinfunction "1_1") (pintype "passive"))
      (node (ref "R176") (pin "1") (pinfunction "1_1") (pintype "passive"))
      (node (ref "R178") (pin "2") (pinfunction "2_2") (pintype "passive"))
      (node (ref "T26") (pin "1") (pinfunction "G_1") (pintype "passive"))
    )
    (net (code "97") (name "Net-(T27-D)") (class "Default")
      (node (ref "LED13") (pin "K") (pinfunction "K_K") (pintype "passive"))
      (node (ref "T27") (pin "3") (pinfunction "D_3") (pintype "passive"))
    )
    (net (code "98") (name "Net-(T29B-D)") (class "Default")
      (node (ref "LED17") (pin "K") (pinfunction "K_K") (pintype "passive"))
      (node (ref "T29") (pin "3") (pinfunction "D_3") (pintype "passive"))
    )
    (net (code "99") (name "unconnected-(IC20-NC-Pad8)") (class "Default")
      (node (ref "IC20") (pin "8") (pinfunction "NC_8") (pintype "power_in+no_connect"))
    )
    (net (code "100") (name "unconnected-(IC20-NC-Pad9)") (class "Default")
      (node (ref "IC20") (pin "9") (pinfunction "NC_9") (pintype "power_in+no_connect"))
    )
    (net (code "101") (name "unconnected-(IC20-NC-Pad10)") (class "Default")
      (node (ref "IC20") (pin "10") (pinfunction "NC_10") (pintype "power_in+no_connect"))
    )
    (net (code "102") (name "unconnected-(IC22-CHG_AL_N-Pad4)") (class "Default")
      (node (ref "IC22") (pin "4") (pinfunction "CHG_AL_N_4") (pintype "passive+no_connect"))
    )
    (net (code "103") (name "unconnected-(IC22-SW_OPEN-Pad1)") (class "Default")
      (node (ref "IC22") (pin "1") (pinfunction "SW_OPEN_1") (pintype "passive+no_connect"))
    )
    (net (code "104") (name "unconnected-(IC23-ALERT#-Pad19)") (class "Default")
      (node (ref "IC23") (pin "19") (pinfunction "ALERT#_19") (pintype "open_collector+no_connect"))
    )
    (net (code "105") (name "unconnected-(IC23-A_B_SIDE#-Pad17)") (class "Default")
      (node (ref "IC23") (pin "17") (pinfunction "A_B_SIDE#_17") (pintype "open_collector+no_connect"))
    )
    (net (code "106") (name "unconnected-(T29A-D-Pad6)") (class "Default")
      (node (ref "T29") (pin "6") (pinfunction "D_6") (pintype "passive+no_connect"))
    )
    (net (code "107") (name "unconnected-(X10A-SBU1-PadA8)") (class "Default")
      (node (ref "X10") (pin "A8") (pinfunction "SBU1_A8") (pintype "passive+no_connect"))
    )
    (net (code "108") (name "unconnected-(X10A-SBU2-PadB8)") (class "Default")
      (node (ref "X10") (pin "B8") (pinfunction "SBU2_B8") (pintype "passive+no_connect"))
    )
    (net (code "109") (name "unconnected-(X10A-SSRXN1-PadB10)") (class "Default")
      (node (ref "X10") (pin "B10") (pinfunction "SSRXN1_B10") (pintype "passive"))
    )
    (net (code "110") (name "unconnected-(X10A-SSRXN2-PadA10)") (class "Default")
      (node (ref "X10") (pin "A10") (pinfunction "SSRXN2_A10") (pintype "passive+no_connect"))
    )
    (net (code "111") (name "unconnected-(X10A-SSRXP1-PadB11)") (class "Default")
      (node (ref "X10") (pin "B11") (pinfunction "SSRXP1_B11") (pintype "passive+no_connect"))
    )
    (net (code "112") (name "unconnected-(X10A-SSRXP2-PadA11)") (class "Default")
      (node (ref "X10") (pin "A11") (pinfunction "SSRXP2_A11") (pintype "passive+no_connect"))
    )
    (net (code "113") (name "unconnected-(X10A-SSTXN1-PadA3)") (class "Default")
      (node (ref "X10") (pin "A3") (pinfunction "SSTXN1_A3") (pintype "passive+no_connect"))
    )
    (net (code "114") (name "unconnected-(X10A-SSTXN2-PadB3)") (class "Default")
      (node (ref "X10") (pin "B3") (pinfunction "SSTXN2_B3") (pintype "passive+no_connect"))
    )
    (net (code "115") (name "unconnected-(X10A-SSTXP1-PadA2)") (class "Default")
      (node (ref "X10") (pin "A2") (pinfunction "SSTXP1_A2") (pintype "passive+no_connect"))
    )
    (net (code "116") (name "unconnected-(X10A-SSTXP2-PadB2)") (class "Default")
      (node (ref "X10") (pin "B2") (pinfunction "SSTXP2_B2") (pintype "passive+no_connect"))
    )
  )
)
